# test_board_logic3.net
KiCad netlist of a schematic drawn in EAGLE
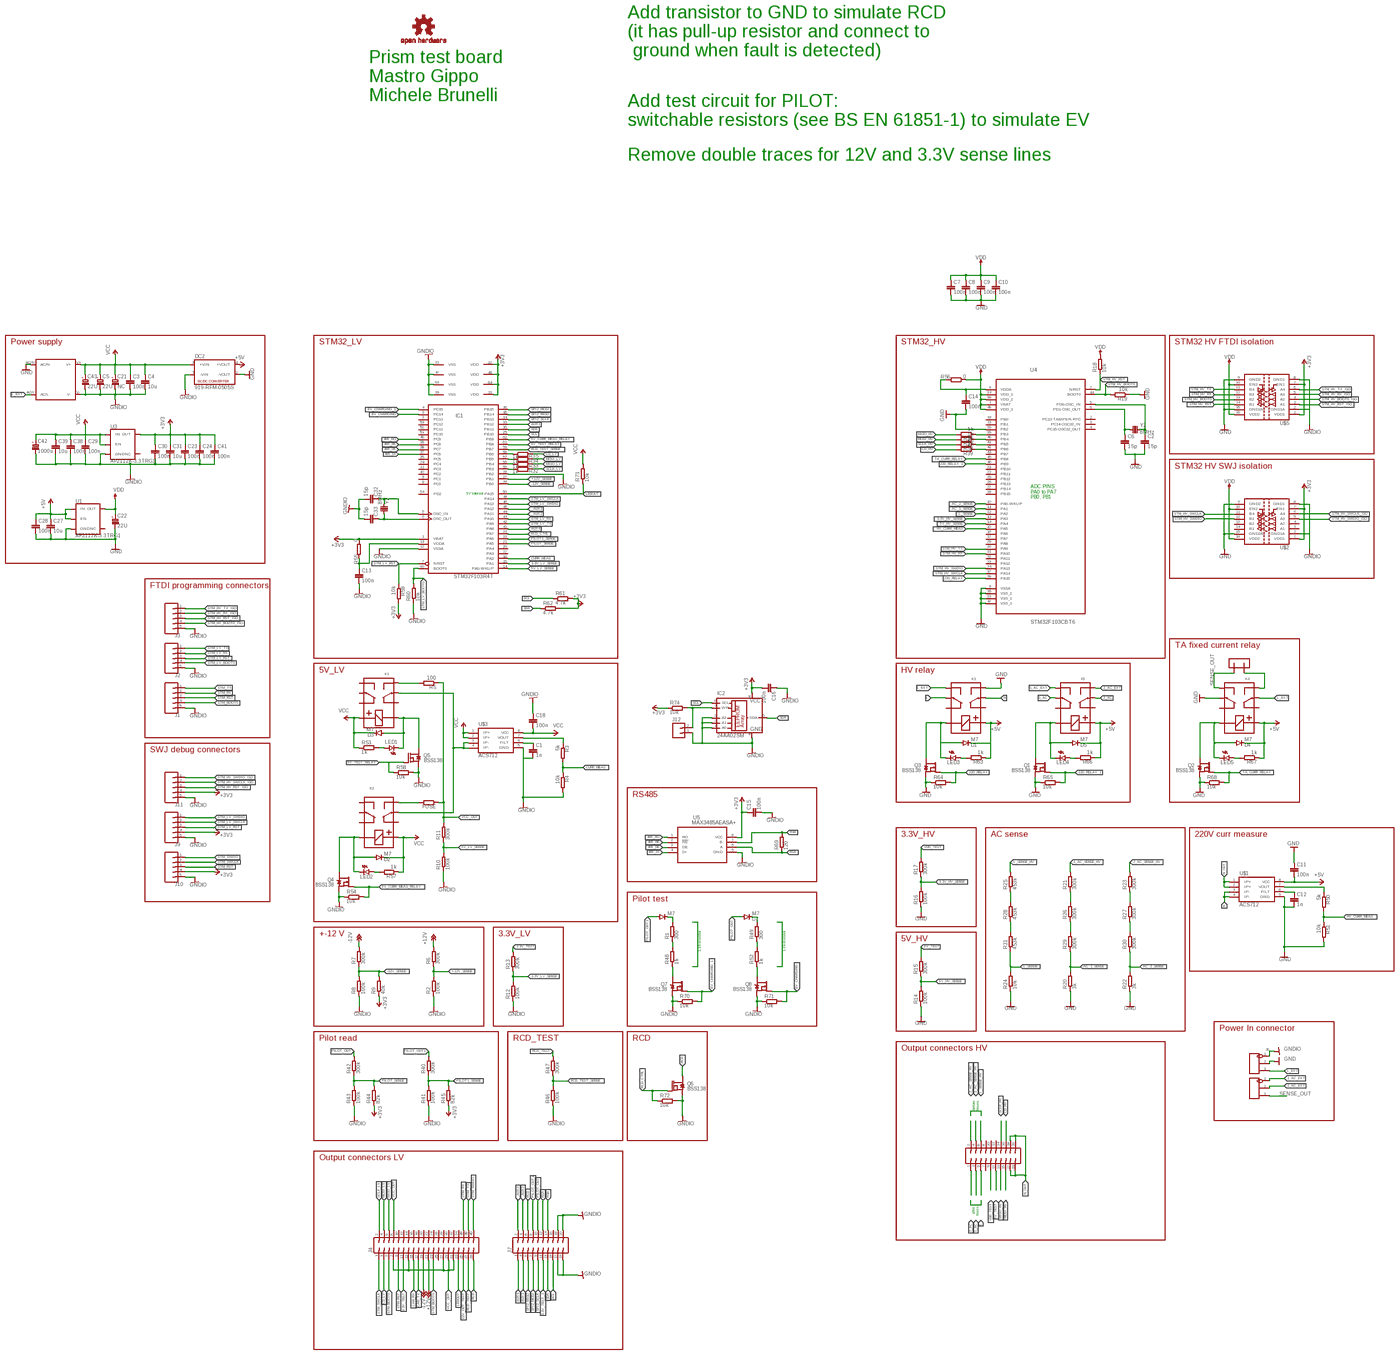
[diagram p0: schematic, sheet 1, overview]
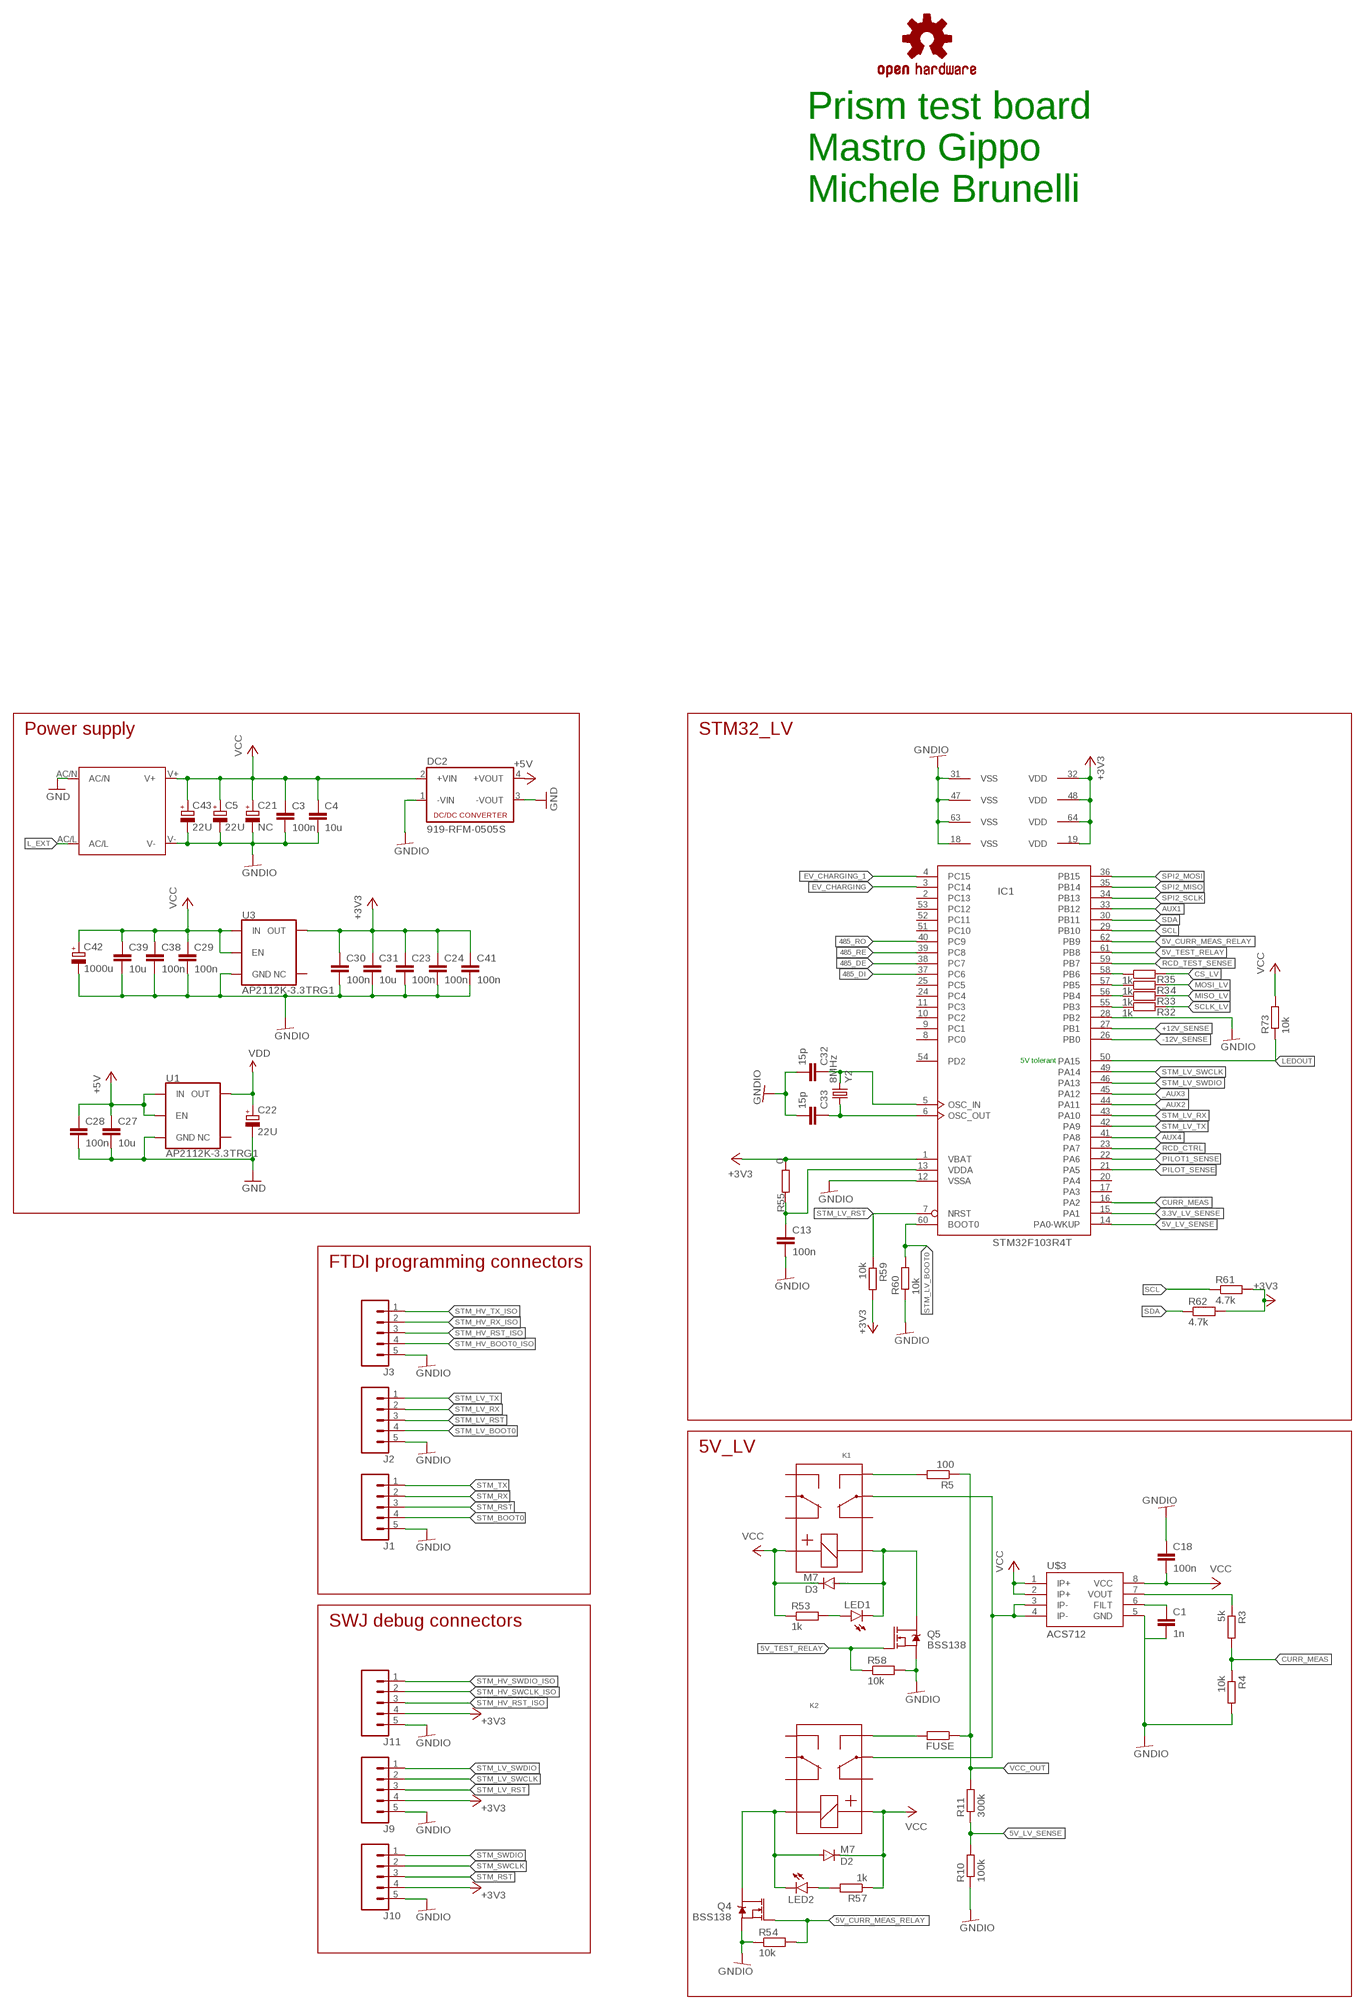
[diagram p1: schematic, sheet 1, part 1 of 4]
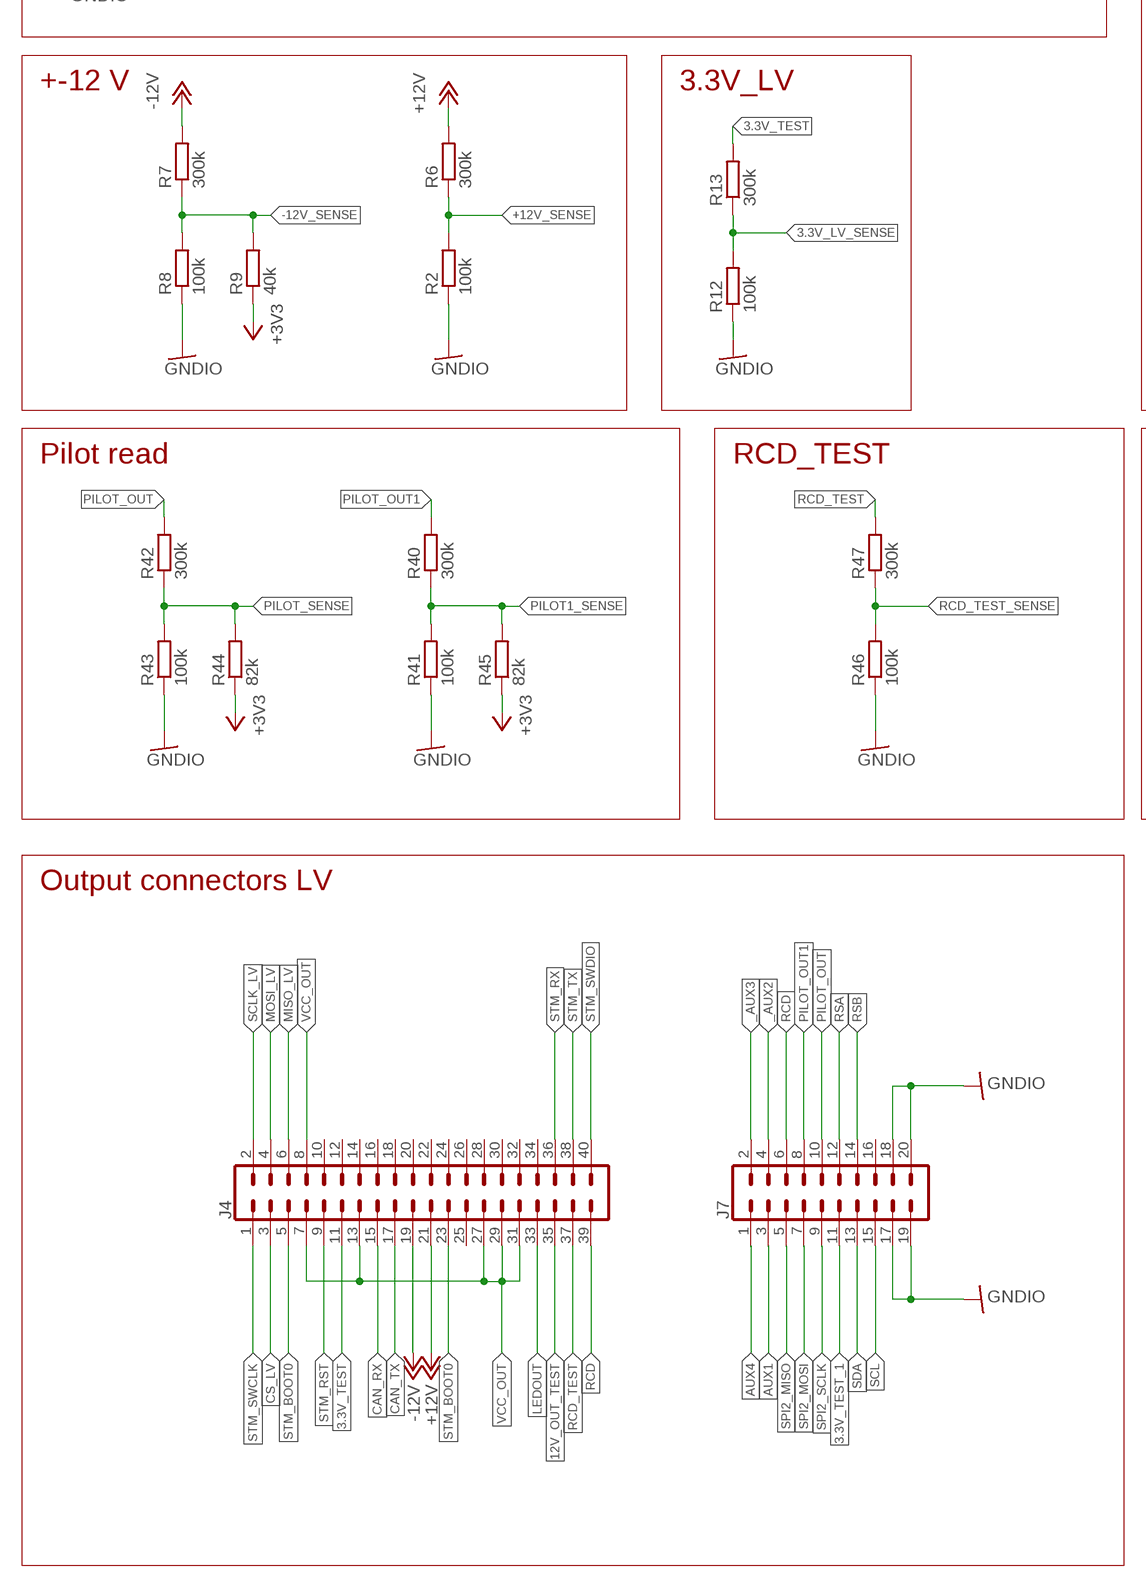
[diagram p2: schematic, sheet 1, part 2 of 4]
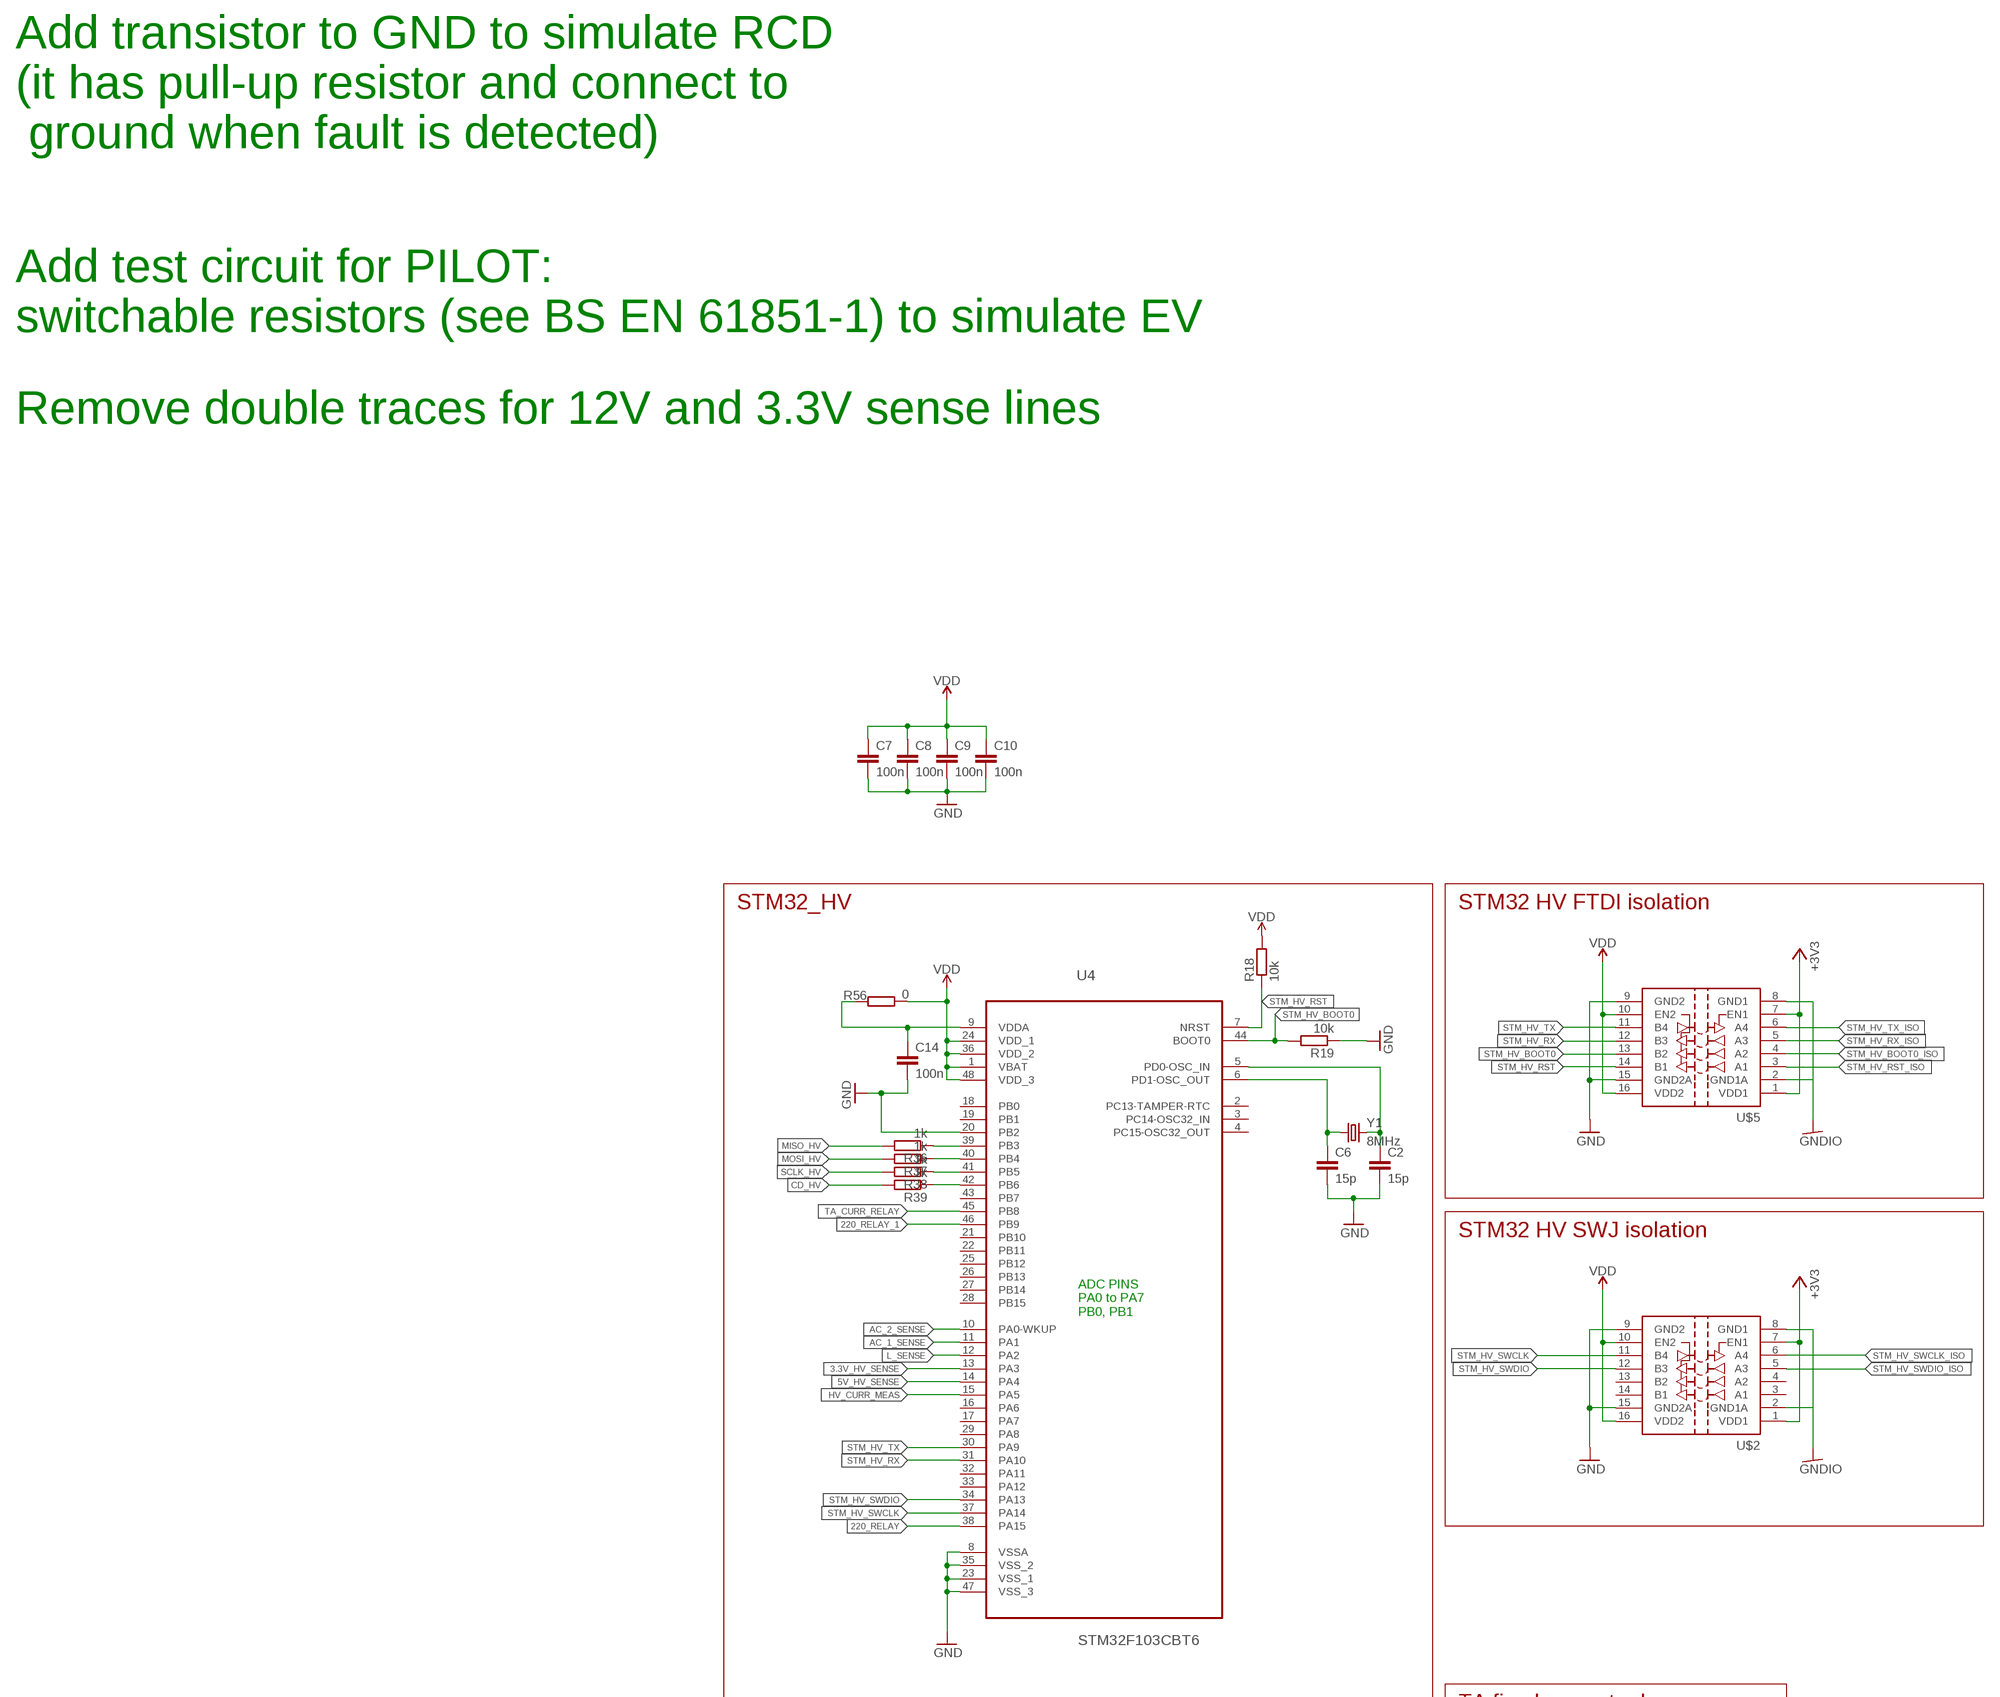
[diagram p3: schematic, sheet 1, part 3 of 4]
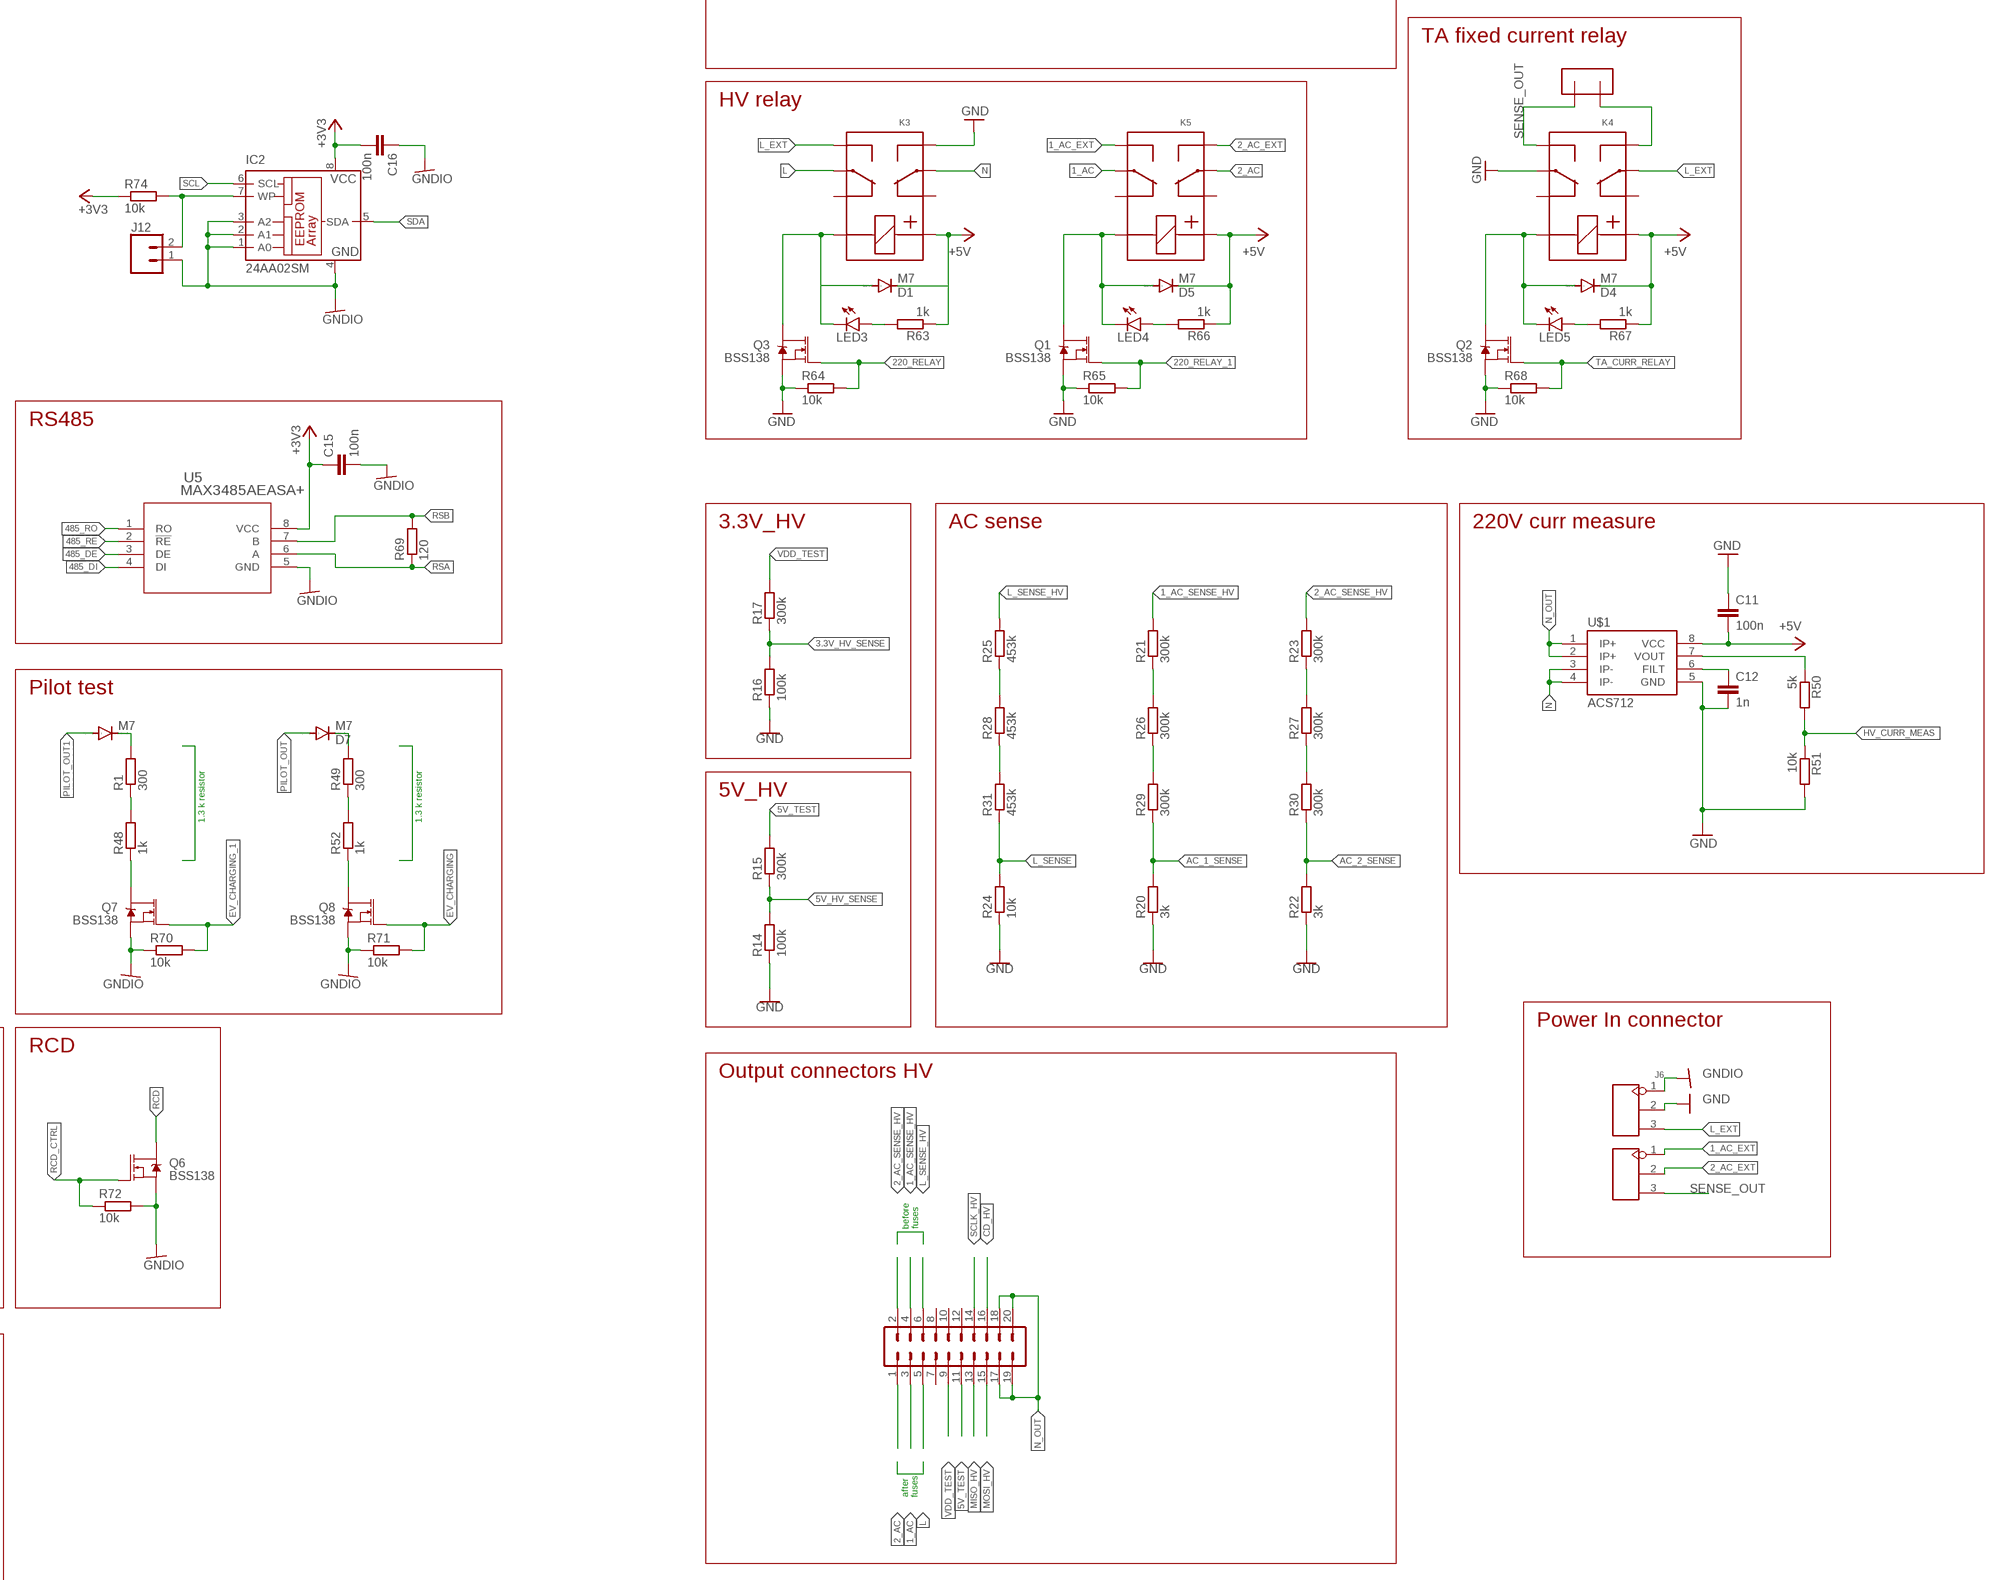
[diagram p4: schematic, sheet 1, part 4 of 4]

(export (version "E")
  (design (tool "Eeschema 10.0.6"))
  (components
    (comp (ref "C1")
      (value "1n")
      (footprint "eagle-import:C0603K")
      (libsource (lib "eagle-import") (part "C-EUC0603K"))
    )
    (comp (ref "C2")
      (value "15p")
      (footprint "eagle-import:C0603K")
      (libsource (lib "eagle-import") (part "C-EUC0603K"))
    )
    (comp (ref "C3")
      (value "100n")
      (footprint "eagle-import:C0603K")
      (libsource (lib "eagle-import") (part "C-EUC0603K"))
    )
    (comp (ref "C4")
      (value "10u")
      (footprint "eagle-import:C0805K")
      (libsource (lib "eagle-import") (part "resistor_348_C-EUC0805K"))
    )
    (comp (ref "C5")
      (value "22U")
      (footprint "eagle-import:B_3528-21R")
      (libsource (lib "eagle-import") (part "CPOL-EUB/3528-21R"))
    )
    (comp (ref "C6")
      (value "15p")
      (footprint "eagle-import:C0603K")
      (libsource (lib "eagle-import") (part "C-EUC0603K"))
    )
    (comp (ref "C7")
      (value "100n")
      (footprint "eagle-import:C0603K")
      (libsource (lib "eagle-import") (part "C-EUC0603K"))
    )
    (comp (ref "C8")
      (value "100n")
      (footprint "eagle-import:C0603K")
      (libsource (lib "eagle-import") (part "C-EUC0603K"))
    )
    (comp (ref "C9")
      (value "100n")
      (footprint "eagle-import:C0603K")
      (libsource (lib "eagle-import") (part "C-EUC0603K"))
    )
    (comp (ref "C10")
      (value "100n")
      (footprint "eagle-import:C0603K")
      (libsource (lib "eagle-import") (part "C-EUC0603K"))
    )
    (comp (ref "C11")
      (value "100n")
      (footprint "eagle-import:C0603K")
      (libsource (lib "eagle-import") (part "C-EUC0603K"))
    )
    (comp (ref "C12")
      (value "1n")
      (footprint "eagle-import:C0603K")
      (libsource (lib "eagle-import") (part "C-EUC0603K"))
    )
    (comp (ref "C13")
      (value "100n")
      (footprint "eagle-import:C0603K")
      (libsource (lib "eagle-import") (part "C-EUC0603K"))
    )
    (comp (ref "C14")
      (value "100n")
      (footprint "eagle-import:C0603K")
      (libsource (lib "eagle-import") (part "C-EUC0603K"))
    )
    (comp (ref "C15")
      (value "100n")
      (footprint "eagle-import:C0603K")
      (libsource (lib "eagle-import") (part "C-EUC0603K"))
    )
    (comp (ref "C16")
      (value "100n")
      (footprint "eagle-import:C0603K")
      (libsource (lib "eagle-import") (part "C-EUC0603K"))
    )
    (comp (ref "C18")
      (value "100n")
      (footprint "eagle-import:C0603K")
      (libsource (lib "eagle-import") (part "C-EUC0603K"))
    )
    (comp (ref "C21")
      (value "NC")
      (footprint "eagle-import:153CLV-0505")
      (libsource (lib "eagle-import") (part "CPOL-EU153CLV-0505"))
    )
    (comp (ref "C22")
      (value "22U")
      (footprint "eagle-import:B_3528-21R")
      (libsource (lib "eagle-import") (part "CPOL-EUB/3528-21R"))
    )
    (comp (ref "C23")
      (value "100n")
      (footprint "eagle-import:C0603K")
      (libsource (lib "eagle-import") (part "C-EUC0603K"))
    )
    (comp (ref "C24")
      (value "100n")
      (footprint "eagle-import:C0603K")
      (libsource (lib "eagle-import") (part "C-EUC0603K"))
    )
    (comp (ref "C27")
      (value "10u")
      (footprint "eagle-import:C0805K")
      (libsource (lib "eagle-import") (part "resistor_348_C-EUC0805K"))
    )
    (comp (ref "C28")
      (value "100n")
      (footprint "eagle-import:C0603K")
      (libsource (lib "eagle-import") (part "C-EUC0603K"))
    )
    (comp (ref "C29")
      (value "100n")
      (footprint "eagle-import:C0603K")
      (libsource (lib "eagle-import") (part "C-EUC0603K"))
    )
    (comp (ref "C30")
      (value "100n")
      (footprint "eagle-import:C0603K")
      (libsource (lib "eagle-import") (part "C-EUC0603K"))
    )
    (comp (ref "C31")
      (value "10u")
      (footprint "eagle-import:C0805K")
      (libsource (lib "eagle-import") (part "resistor_348_C-EUC0805K"))
    )
    (comp (ref "C32")
      (value "15p")
      (footprint "eagle-import:C0603K")
      (libsource (lib "eagle-import") (part "C-EUC0603K"))
    )
    (comp (ref "C33")
      (value "15p")
      (footprint "eagle-import:C0603K")
      (libsource (lib "eagle-import") (part "C-EUC0603K"))
    )
    (comp (ref "C38")
      (value "100n")
      (footprint "eagle-import:C0603K")
      (libsource (lib "eagle-import") (part "C-EUC0603K"))
    )
    (comp (ref "C39")
      (value "10u")
      (footprint "eagle-import:C0805K")
      (libsource (lib "eagle-import") (part "resistor_348_C-EUC0805K"))
    )
    (comp (ref "C41")
      (value "100n")
      (footprint "eagle-import:C0603K")
      (libsource (lib "eagle-import") (part "C-EUC0603K"))
    )
    (comp (ref "C42")
      (value "1000u")
      (footprint "eagle-import:E5-10,5")
      (libsource (lib "eagle-import") (part "CPOL-EUE5-10.5"))
    )
    (comp (ref "C43")
      (value "22U")
      (footprint "eagle-import:B_3528-21R")
      (libsource (lib "eagle-import") (part "CPOL-EUB/3528-21R"))
    )
    (comp (ref "D1")
      (value "M7")
      (footprint "eagle-import:DO-214AC")
      (libsource (lib "eagle-import") (part "DIODE-DO-214AC"))
    )
    (comp (ref "D2")
      (value "M7")
      (footprint "eagle-import:DO-214AC")
      (libsource (lib "eagle-import") (part "DIODE-DO-214AC"))
    )
    (comp (ref "D3")
      (value "M7")
      (footprint "eagle-import:DO-214AC")
      (libsource (lib "eagle-import") (part "DIODE-DO-214AC"))
    )
    (comp (ref "D4")
      (value "M7")
      (footprint "eagle-import:DO-214AC")
      (libsource (lib "eagle-import") (part "DIODE-DO-214AC"))
    )
    (comp (ref "D5")
      (value "M7")
      (footprint "eagle-import:DO-214AC")
      (libsource (lib "eagle-import") (part "DIODE-DO-214AC"))
    )
    (comp (ref "D6")
      (value "M7")
      (footprint "eagle-import:DO-214AC")
      (libsource (lib "eagle-import") (part "DIODE-DO-214AC"))
    )
    (comp (ref "D7")
      (value "M7")
      (footprint "eagle-import:DO-214AC")
      (libsource (lib "eagle-import") (part "DIODE-DO-214AC"))
    )
    (comp (ref "DC2")
      (value "919-RFM-0505S")
      (footprint "eagle-import:NME")
      (fields (field (name "MF") "C & D TECHNOLOGIES, INC") (field (name "MPN") "NME1205D"))
      (libsource (lib "eagle-import") (part "NME"))
    )
    (comp (ref "FUSE")
      (value "R-EU_R0805")
      (footprint "eagle-import:R0805")
      (libsource (lib "eagle-import") (part "R-EU_R0805"))
    )
    (comp (ref "IC1")
      (value "STM32F103R4T")
      (footprint "eagle-import:LQFP64")
      (libsource (lib "eagle-import") (part "STM32F103RT4"))
    )
    (comp (ref "IC2")
      (value "24AA02SM")
      (footprint "eagle-import:SO-08M")
      (fields (field (name "MF") "MICROCHIP") (field (name "MPN") "24AA02-I/SN"))
      (libsource (lib "eagle-import") (part "24SMAA02"))
    )
    (comp (ref "J1")
      (value "2001R-5P")
      (footprint "eagle-import:JST-5-PTH-VERT")
      (libsource (lib "eagle-import") (part "CONN_05JST-VERT"))
    )
    (comp (ref "J2")
      (value "2001R-5P")
      (footprint "eagle-import:JST-5-PTH-VERT")
      (libsource (lib "eagle-import") (part "CONN_05JST-VERT"))
    )
    (comp (ref "J3")
      (value "2001R-5P")
      (footprint "eagle-import:JST-5-PTH-VERT")
      (libsource (lib "eagle-import") (part "CONN_05JST-VERT"))
    )
    (comp (ref "J4")
      (value "CONN_20X2SHROUDED")
      (footprint "eagle-import:2X20_SHROUDED")
      (libsource (lib "eagle-import") (part "CONN_20X2SHROUDED"))
    )
    (comp (ref "J5")
      (value "GREEN-3P-5.0")
      (footprint "eagle-import:H3-5.0-15.5X8.0MM")
      (libsource (lib "eagle-import") (part "SCREW-TERMINAL-GREEN(3P-5.0)"))
    )
    (comp (ref "J6")
      (value "GREEN-3P-5.0")
      (footprint "eagle-import:H3-5.0-15.5X8.0MM")
      (libsource (lib "eagle-import") (part "SCREW-TERMINAL-GREEN(3P-5.0)"))
    )
    (comp (ref "J7")
      (value "CONN_10X2")
      (footprint "eagle-import:2X10")
      (libsource (lib "eagle-import") (part "CONN_10X2"))
    )
    (comp (ref "J8")
      (value "CONN_10X2")
      (footprint "eagle-import:2X10")
      (libsource (lib "eagle-import") (part "CONN_10X2"))
    )
    (comp (ref "J9")
      (value "2001R-5P")
      (footprint "eagle-import:JST-5-PTH-VERT")
      (libsource (lib "eagle-import") (part "CONN_05JST-VERT"))
    )
    (comp (ref "J10")
      (value "2001R-5P")
      (footprint "eagle-import:JST-5-PTH-VERT")
      (libsource (lib "eagle-import") (part "CONN_05JST-VERT"))
    )
    (comp (ref "J11")
      (value "2001R-5P")
      (footprint "eagle-import:JST-5-PTH-VERT")
      (libsource (lib "eagle-import") (part "CONN_05JST-VERT"))
    )
    (comp (ref "J12")
      (value "CONN_02")
      (footprint "eagle-import:1X02")
      (libsource (lib "eagle-import") (part "CONN_02"))
    )
    (comp (ref "K1")
      (value "G6S-2")
      (footprint "eagle-import:G6S-2")
      (libsource (lib "eagle-import") (part "G6S-2"))
    )
    (comp (ref "K2")
      (value "G6S-2")
      (footprint "eagle-import:G6S-2")
      (libsource (lib "eagle-import") (part "G6S-2"))
    )
    (comp (ref "K3")
      (value "G6S-2")
      (footprint "eagle-import:G6S-2")
      (libsource (lib "eagle-import") (part "G6S-2"))
    )
    (comp (ref "K4")
      (value "G6S-2")
      (footprint "eagle-import:G6S-2")
      (libsource (lib "eagle-import") (part "G6S-2"))
    )
    (comp (ref "K5")
      (value "G6S-2")
      (footprint "eagle-import:G6S-2")
      (libsource (lib "eagle-import") (part "G6S-2"))
    )
    (comp (ref "LED1")
      (value "LEDSMT1206")
      (footprint "eagle-import:1206")
      (libsource (lib "eagle-import") (part "LEDSMT1206"))
    )
    (comp (ref "LED2")
      (value "LEDSMT1206")
      (footprint "eagle-import:1206")
      (libsource (lib "eagle-import") (part "LEDSMT1206"))
    )
    (comp (ref "LED3")
      (value "LEDSMT1206")
      (footprint "eagle-import:1206")
      (libsource (lib "eagle-import") (part "LEDSMT1206"))
    )
    (comp (ref "LED4")
      (value "LEDSMT1206")
      (footprint "eagle-import:1206")
      (libsource (lib "eagle-import") (part "LEDSMT1206"))
    )
    (comp (ref "LED5")
      (value "LEDSMT1206")
      (footprint "eagle-import:1206")
      (libsource (lib "eagle-import") (part "LEDSMT1206"))
    )
    (comp (ref "Q1")
      (value "BSS138")
      (footprint "eagle-import:SOT23-3")
      (libsource (lib "eagle-import") (part "MOSFET-NCH-BSS138"))
    )
    (comp (ref "Q2")
      (value "BSS138")
      (footprint "eagle-import:SOT23-3")
      (libsource (lib "eagle-import") (part "MOSFET-NCH-BSS138"))
    )
    (comp (ref "Q3")
      (value "BSS138")
      (footprint "eagle-import:SOT23-3")
      (libsource (lib "eagle-import") (part "MOSFET-NCH-BSS138"))
    )
    (comp (ref "Q4")
      (value "BSS138")
      (footprint "eagle-import:SOT23-3")
      (libsource (lib "eagle-import") (part "MOSFET-NCH-BSS138"))
    )
    (comp (ref "Q5")
      (value "BSS138")
      (footprint "eagle-import:SOT23-3")
      (libsource (lib "eagle-import") (part "MOSFET-NCH-BSS138"))
    )
    (comp (ref "Q6")
      (value "BSS138")
      (footprint "eagle-import:SOT23-3")
      (libsource (lib "eagle-import") (part "MOSFET-NCH-BSS138"))
    )
    (comp (ref "Q7")
      (value "BSS138")
      (footprint "eagle-import:SOT23-3")
      (libsource (lib "eagle-import") (part "MOSFET-NCH-BSS138"))
    )
    (comp (ref "Q8")
      (value "BSS138")
      (footprint "eagle-import:SOT23-3")
      (libsource (lib "eagle-import") (part "MOSFET-NCH-BSS138"))
    )
    (comp (ref "R1")
      (value "300")
      (footprint "eagle-import:R0603")
      (libsource (lib "eagle-import") (part "R-EU_R0603"))
    )
    (comp (ref "R2")
      (value "100k")
      (footprint "eagle-import:R0603")
      (libsource (lib "eagle-import") (part "R-EU_R0603"))
    )
    (comp (ref "R3")
      (value "5k")
      (footprint "eagle-import:R0603")
      (libsource (lib "eagle-import") (part "R-EU_R0603"))
    )
    (comp (ref "R4")
      (value "10k")
      (footprint "eagle-import:R0603")
      (libsource (lib "eagle-import") (part "R-EU_R0603"))
    )
    (comp (ref "R5")
      (value "100")
      (footprint "eagle-import:R1210")
      (libsource (lib "eagle-import") (part "R-EU_R1210"))
    )
    (comp (ref "R6")
      (value "300k")
      (footprint "eagle-import:R0603")
      (libsource (lib "eagle-import") (part "R-EU_R0603"))
    )
    (comp (ref "R7")
      (value "300k")
      (footprint "eagle-import:R0603")
      (libsource (lib "eagle-import") (part "R-EU_R0603"))
    )
    (comp (ref "R8")
      (value "100k")
      (footprint "eagle-import:R0603")
      (libsource (lib "eagle-import") (part "R-EU_R0603"))
    )
    (comp (ref "R9")
      (value "40k")
      (footprint "eagle-import:R0603")
      (libsource (lib "eagle-import") (part "R-EU_R0603"))
    )
    (comp (ref "R10")
      (value "100k")
      (footprint "eagle-import:R0603")
      (libsource (lib "eagle-import") (part "R-EU_R0603"))
    )
    (comp (ref "R11")
      (value "300k")
      (footprint "eagle-import:R0603")
      (libsource (lib "eagle-import") (part "R-EU_R0603"))
    )
    (comp (ref "R12")
      (value "100k")
      (footprint "eagle-import:R0603")
      (libsource (lib "eagle-import") (part "R-EU_R0603"))
    )
    (comp (ref "R13")
      (value "300k")
      (footprint "eagle-import:R0603")
      (libsource (lib "eagle-import") (part "R-EU_R0603"))
    )
    (comp (ref "R14")
      (value "100k")
      (footprint "eagle-import:R0603")
      (libsource (lib "eagle-import") (part "R-EU_R0603"))
    )
    (comp (ref "R15")
      (value "300k")
      (footprint "eagle-import:R0603")
      (libsource (lib "eagle-import") (part "R-EU_R0603"))
    )
    (comp (ref "R16")
      (value "100k")
      (footprint "eagle-import:R0603")
      (libsource (lib "eagle-import") (part "R-EU_R0603"))
    )
    (comp (ref "R17")
      (value "300k")
      (footprint "eagle-import:R0603")
      (libsource (lib "eagle-import") (part "R-EU_R0603"))
    )
    (comp (ref "R18")
      (value "10k")
      (footprint "eagle-import:R0603")
      (libsource (lib "eagle-import") (part "R-EU_R0603"))
    )
    (comp (ref "R19")
      (value "10k")
      (footprint "eagle-import:R0603")
      (libsource (lib "eagle-import") (part "R-EU_R0603"))
    )
    (comp (ref "R20")
      (value "3k")
      (footprint "eagle-import:R0603")
      (libsource (lib "eagle-import") (part "R-EU_R0603"))
    )
    (comp (ref "R21")
      (value "300k")
      (footprint "eagle-import:R0603")
      (libsource (lib "eagle-import") (part "R-EU_R0603"))
    )
    (comp (ref "R22")
      (value "3k")
      (footprint "eagle-import:R0603")
      (libsource (lib "eagle-import") (part "R-EU_R0603"))
    )
    (comp (ref "R23")
      (value "300k")
      (footprint "eagle-import:R0603")
      (libsource (lib "eagle-import") (part "R-EU_R0603"))
    )
    (comp (ref "R24")
      (value "10k")
      (footprint "eagle-import:R0603")
      (libsource (lib "eagle-import") (part "R-EU_R0603"))
    )
    (comp (ref "R25")
      (value "453k")
      (footprint "eagle-import:R0603")
      (libsource (lib "eagle-import") (part "R-EU_R0603"))
    )
    (comp (ref "R26")
      (value "300k")
      (footprint "eagle-import:R0603")
      (libsource (lib "eagle-import") (part "R-EU_R0603"))
    )
    (comp (ref "R27")
      (value "300k")
      (footprint "eagle-import:R0603")
      (libsource (lib "eagle-import") (part "R-EU_R0603"))
    )
    (comp (ref "R28")
      (value "453k")
      (footprint "eagle-import:R0603")
      (libsource (lib "eagle-import") (part "R-EU_R0603"))
    )
    (comp (ref "R29")
      (value "300k")
      (footprint "eagle-import:R0603")
      (libsource (lib "eagle-import") (part "R-EU_R0603"))
    )
    (comp (ref "R30")
      (value "300k")
      (footprint "eagle-import:R0603")
      (libsource (lib "eagle-import") (part "R-EU_R0603"))
    )
    (comp (ref "R31")
      (value "453k")
      (footprint "eagle-import:R0603")
      (libsource (lib "eagle-import") (part "R-EU_R0603"))
    )
    (comp (ref "R32")
      (value "1k")
      (footprint "eagle-import:R0603")
      (libsource (lib "eagle-import") (part "R-EU_R0603"))
    )
    (comp (ref "R33")
      (value "1k")
      (footprint "eagle-import:R0603")
      (libsource (lib "eagle-import") (part "R-EU_R0603"))
    )
    (comp (ref "R34")
      (value "1k")
      (footprint "eagle-import:R0603")
      (libsource (lib "eagle-import") (part "R-EU_R0603"))
    )
    (comp (ref "R35")
      (value "1k")
      (footprint "eagle-import:R0603")
      (libsource (lib "eagle-import") (part "R-EU_R0603"))
    )
    (comp (ref "R36")
      (value "1k")
      (footprint "eagle-import:R0603")
      (libsource (lib "eagle-import") (part "R-EU_R0603"))
    )
    (comp (ref "R37")
      (value "1k")
      (footprint "eagle-import:R0603")
      (libsource (lib "eagle-import") (part "R-EU_R0603"))
    )
    (comp (ref "R38")
      (value "1k")
      (footprint "eagle-import:R0603")
      (libsource (lib "eagle-import") (part "R-EU_R0603"))
    )
    (comp (ref "R39")
      (value "1k")
      (footprint "eagle-import:R0603")
      (libsource (lib "eagle-import") (part "R-EU_R0603"))
    )
    (comp (ref "R40")
      (value "300k")
      (footprint "eagle-import:R0603")
      (libsource (lib "eagle-import") (part "R-EU_R0603"))
    )
    (comp (ref "R41")
      (value "100k")
      (footprint "eagle-import:R0603")
      (libsource (lib "eagle-import") (part "R-EU_R0603"))
    )
    (comp (ref "R42")
      (value "300k")
      (footprint "eagle-import:R0603")
      (libsource (lib "eagle-import") (part "R-EU_R0603"))
    )
    (comp (ref "R43")
      (value "100k")
      (footprint "eagle-import:R0603")
      (libsource (lib "eagle-import") (part "R-EU_R0603"))
    )
    (comp (ref "R44")
      (value "82k")
      (footprint "eagle-import:R0603")
      (libsource (lib "eagle-import") (part "R-EU_R0603"))
    )
    (comp (ref "R45")
      (value "82k")
      (footprint "eagle-import:R0603")
      (libsource (lib "eagle-import") (part "R-EU_R0603"))
    )
    (comp (ref "R46")
      (value "100k")
      (footprint "eagle-import:R0603")
      (libsource (lib "eagle-import") (part "R-EU_R0603"))
    )
    (comp (ref "R47")
      (value "300k")
      (footprint "eagle-import:R0603")
      (libsource (lib "eagle-import") (part "R-EU_R0603"))
    )
    (comp (ref "R48")
      (value "1k")
      (footprint "eagle-import:R0603")
      (libsource (lib "eagle-import") (part "R-EU_R0603"))
    )
    (comp (ref "R49")
      (value "300")
      (footprint "eagle-import:R0603")
      (libsource (lib "eagle-import") (part "R-EU_R0603"))
    )
    (comp (ref "R50")
      (value "5k")
      (footprint "eagle-import:R0603")
      (libsource (lib "eagle-import") (part "R-EU_R0603"))
    )
    (comp (ref "R51")
      (value "10k")
      (footprint "eagle-import:R0603")
      (libsource (lib "eagle-import") (part "R-EU_R0603"))
    )
    (comp (ref "R52")
      (value "1k")
      (footprint "eagle-import:R0603")
      (libsource (lib "eagle-import") (part "R-EU_R0603"))
    )
    (comp (ref "R53")
      (value "1k")
      (footprint "eagle-import:R0603")
      (libsource (lib "eagle-import") (part "R-EU_R0603"))
    )
    (comp (ref "R54")
      (value "10k")
      (footprint "eagle-import:R0603")
      (libsource (lib "eagle-import") (part "R-EU_R0603"))
    )
    (comp (ref "R55")
      (value "0")
      (footprint "eagle-import:R0603")
      (libsource (lib "eagle-import") (part "R-EU_R0603"))
    )
    (comp (ref "R56")
      (value "0")
      (footprint "eagle-import:R0603")
      (libsource (lib "eagle-import") (part "R-EU_R0603"))
    )
    (comp (ref "R57")
      (value "1k")
      (footprint "eagle-import:R0603")
      (libsource (lib "eagle-import") (part "R-EU_R0603"))
    )
    (comp (ref "R58")
      (value "10k")
      (footprint "eagle-import:R0603")
      (libsource (lib "eagle-import") (part "R-EU_R0603"))
    )
    (comp (ref "R59")
      (value "10k")
      (footprint "eagle-import:R0603")
      (libsource (lib "eagle-import") (part "R-EU_R0603"))
    )
    (comp (ref "R60")
      (value "10k")
      (footprint "eagle-import:R0603")
      (libsource (lib "eagle-import") (part "R-EU_R0603"))
    )
    (comp (ref "R61")
      (value "4.7k")
      (footprint "eagle-import:R0603")
      (libsource (lib "eagle-import") (part "R-EU_R0603"))
    )
    (comp (ref "R62")
      (value "4.7k")
      (footprint "eagle-import:R0603")
      (libsource (lib "eagle-import") (part "R-EU_R0603"))
    )
    (comp (ref "R63")
      (value "1k")
      (footprint "eagle-import:R0603")
      (libsource (lib "eagle-import") (part "R-EU_R0603"))
    )
    (comp (ref "R64")
      (value "10k")
      (footprint "eagle-import:R0603")
      (libsource (lib "eagle-import") (part "R-EU_R0603"))
    )
    (comp (ref "R65")
      (value "10k")
      (footprint "eagle-import:R0603")
      (libsource (lib "eagle-import") (part "R-EU_R0603"))
    )
    (comp (ref "R66")
      (value "1k")
      (footprint "eagle-import:R0603")
      (libsource (lib "eagle-import") (part "R-EU_R0603"))
    )
    (comp (ref "R67")
      (value "1k")
      (footprint "eagle-import:R0603")
      (libsource (lib "eagle-import") (part "R-EU_R0603"))
    )
    (comp (ref "R68")
      (value "10k")
      (footprint "eagle-import:R0603")
      (libsource (lib "eagle-import") (part "R-EU_R0603"))
    )
    (comp (ref "R69")
      (value "120")
      (footprint "eagle-import:R0603")
      (libsource (lib "eagle-import") (part "R-EU_R0603"))
    )
    (comp (ref "R70")
      (value "10k")
      (footprint "eagle-import:R0603")
      (libsource (lib "eagle-import") (part "R-EU_R0603"))
    )
    (comp (ref "R71")
      (value "10k")
      (footprint "eagle-import:R0603")
      (libsource (lib "eagle-import") (part "R-EU_R0603"))
    )
    (comp (ref "R72")
      (value "10k")
      (footprint "eagle-import:R0603")
      (libsource (lib "eagle-import") (part "R-EU_R0603"))
    )
    (comp (ref "R73")
      (value "10k")
      (footprint "eagle-import:R0603")
      (libsource (lib "eagle-import") (part "R-EU_R0603"))
    )
    (comp (ref "R74")
      (value "10k")
      (footprint "eagle-import:R0603")
      (libsource (lib "eagle-import") (part "R-EU_R0603"))
    )
    (comp (ref "U$1")
      (value "ACS712")
      (footprint "eagle-import:SO08")
      (libsource (lib "eagle-import") (part "ACS712"))
    )
    (comp (ref "U$2")
      (value "SI8441IS1")
      (footprint "eagle-import:SO16")
      (libsource (lib "eagle-import") (part "SI8441IS1"))
    )
    (comp (ref "U$3")
      (value "ACS712")
      (footprint "eagle-import:SO08")
      (libsource (lib "eagle-import") (part "ACS712"))
    )
    (comp (ref "U$4")
      (value "NC")
      (footprint "eagle-import:IRM_15_20")
      (libsource (lib "eagle-import") (part "IRM_15/20IRM_15/20"))
    )
    (comp (ref "U$5")
      (value "SI8441IS1")
      (footprint "eagle-import:SO16")
      (libsource (lib "eagle-import") (part "SI8441IS1"))
    )
    (comp (ref "U$6")
      (value "2 PIN STRIP F")
      (footprint "eagle-import:STRIP_NOMIDDLE")
      (libsource (lib "eagle-import") (part "ISOLATED_2P"))
    )
    (comp (ref "U$7")
      (value "OSHW-LOGOL")
      (footprint "eagle-import:OSHW-LOGO-L")
      (libsource (lib "eagle-import") (part "OSHW-LOGOL"))
    )
    (comp (ref "U1")
      (value "AP2112K-3.3TRG1")
      (footprint "eagle-import:SOT23-5")
      (libsource (lib "eagle-import") (part "V_REG_AP2112K-3.3V"))
    )
    (comp (ref "U3")
      (value "AP2112K-3.3TRG1")
      (footprint "eagle-import:SOT23-5")
      (libsource (lib "eagle-import") (part "V_REG_AP2112K-3.3V"))
    )
    (comp (ref "U4")
      (value "STM32F103CBT6")
      (footprint "eagle-import:QFP50P900X900X160-48N")
      (libsource (lib "eagle-import") (part "STM32F103CBT6"))
    )
    (comp (ref "U5")
      (value "MAX3485AEASA+")
      (footprint "eagle-import:21-0041B_8")
      (libsource (lib "eagle-import") (part "MAX3485AEASA+"))
    )
    (comp (ref "Y1")
      (value "8MHz")
      (footprint "eagle-import:CRYSTAL-SMD-3.2X2.5MM")
      (libsource (lib "eagle-import") (part "CRYSTALSMD-3.2X2.5"))
    )
    (comp (ref "Y2")
      (value "8MHz")
      (footprint "eagle-import:CRYSTAL-SMD-3.2X2.5MM")
      (libsource (lib "eagle-import") (part "CRYSTALSMD-3.2X2.5"))
    )
  )
  (nets
    (net (code "1") (name "+3V3") (class "Default")
      (node (ref "C15") (pin "1") (pinfunction "1_1") (pintype "passive"))
      (node (ref "C16") (pin "2") (pinfunction "2_2") (pintype "passive"))
      (node (ref "C23") (pin "1") (pinfunction "1_1") (pintype "passive"))
      (node (ref "C24") (pin "1") (pinfunction "1_1") (pintype "passive"))
      (node (ref "C30") (pin "1") (pinfunction "1_1") (pintype "passive"))
      (node (ref "C31") (pin "1") (pinfunction "1_1") (pintype "passive"))
      (node (ref "C41") (pin "1") (pinfunction "1_1") (pintype "passive"))
      (node (ref "IC1") (pin "1") (pinfunction "VBAT_1") (pintype "power_in"))
      (node (ref "IC1") (pin "19") (pinfunction "VDD_19") (pintype "power_in"))
      (node (ref "IC1") (pin "32") (pinfunction "VDD_32") (pintype "power_in"))
      (node (ref "IC1") (pin "48") (pinfunction "VDD_48") (pintype "power_in"))
      (node (ref "IC1") (pin "64") (pinfunction "VDD_64") (pintype "power_in"))
      (node (ref "IC2") (pin "8") (pinfunction "VCC_8") (pintype "power_in"))
      (node (ref "J10") (pin "4") (pinfunction "4_4") (pintype "passive"))
      (node (ref "J11") (pin "4") (pinfunction "4_4") (pintype "passive"))
      (node (ref "J9") (pin "4") (pinfunction "4_4") (pintype "passive"))
      (node (ref "R44") (pin "1") (pinfunction "1_1") (pintype "passive"))
      (node (ref "R45") (pin "1") (pinfunction "1_1") (pintype "passive"))
      (node (ref "R55") (pin "1") (pinfunction "1_1") (pintype "passive"))
      (node (ref "R59") (pin "2") (pinfunction "2_2") (pintype "passive"))
      (node (ref "R61") (pin "2") (pinfunction "2_2") (pintype "passive"))
      (node (ref "R62") (pin "2") (pinfunction "2_2") (pintype "passive"))
      (node (ref "R74") (pin "1") (pinfunction "1_1") (pintype "passive"))
      (node (ref "R9") (pin "1") (pinfunction "1_1") (pintype "passive"))
      (node (ref "U$2") (pin "1") (pinfunction "VDD1_1") (pintype "power_in"))
      (node (ref "U$2") (pin "7") (pinfunction "EN1_7") (pintype "input"))
      (node (ref "U$5") (pin "1") (pinfunction "VDD1_1") (pintype "power_in"))
      (node (ref "U$5") (pin "7") (pinfunction "EN1_7") (pintype "input"))
      (node (ref "U3") (pin "5") (pinfunction "OUT_5") (pintype "passive"))
      (node (ref "U5") (pin "8") (pinfunction "VCC_8") (pintype "power_in"))
    )
    (net (code "2") (name "+5V") (class "Default")
      (node (ref "C11") (pin "2") (pinfunction "2_2") (pintype "passive"))
      (node (ref "C27") (pin "1") (pinfunction "1_1") (pintype "passive"))
      (node (ref "C28") (pin "1") (pinfunction "1_1") (pintype "passive"))
      (node (ref "D1") (pin "C") (pinfunction "C_C") (pintype "passive"))
      (node (ref "D4") (pin "C") (pinfunction "C_C") (pintype "passive"))
      (node (ref "D5") (pin "C") (pinfunction "C_C") (pintype "passive"))
      (node (ref "DC2") (pin "4") (pinfunction "+VOUT_4") (pintype "passive"))
      (node (ref "K3") (pin "1") (pinfunction "1_1") (pintype "passive"))
      (node (ref "K4") (pin "1") (pinfunction "1_1") (pintype "passive"))
      (node (ref "K5") (pin "1") (pinfunction "1_1") (pintype "passive"))
      (node (ref "R63") (pin "1") (pinfunction "1_1") (pintype "passive"))
      (node (ref "R66") (pin "1") (pinfunction "1_1") (pintype "passive"))
      (node (ref "R67") (pin "1") (pinfunction "1_1") (pintype "passive"))
      (node (ref "U$1") (pin "8") (pinfunction "VCC_8") (pintype "bidirectional"))
      (node (ref "U1") (pin "1") (pinfunction "IN_1") (pintype "input"))
      (node (ref "U1") (pin "3") (pinfunction "EN_3") (pintype "input"))
    )
    (net (code "3") (name "+12V") (class "Default")
      (node (ref "J4") (pin "21") (pinfunction "21_21") (pintype "passive"))
      (node (ref "R6") (pin "2") (pinfunction "2_2") (pintype "passive"))
    )
    (net (code "4") (name "+12V_SENSE") (class "Default")
      (node (ref "IC1") (pin "27") (pinfunction "PB1_27") (pintype "bidirectional"))
      (node (ref "R2") (pin "2") (pinfunction "2_2") (pintype "passive"))
      (node (ref "R6") (pin "1") (pinfunction "1_1") (pintype "passive"))
    )
    (net (code "5") (name "-12V") (class "Default")
      (node (ref "J4") (pin "19") (pinfunction "19_19") (pintype "passive"))
      (node (ref "R7") (pin "2") (pinfunction "2_2") (pintype "passive"))
    )
    (net (code "6") (name "-12V_SENSE") (class "Default")
      (node (ref "IC1") (pin "26") (pinfunction "PB0_26") (pintype "bidirectional"))
      (node (ref "R7") (pin "1") (pinfunction "1_1") (pintype "passive"))
      (node (ref "R8") (pin "2") (pinfunction "2_2") (pintype "passive"))
      (node (ref "R9") (pin "2") (pinfunction "2_2") (pintype "passive"))
    )
    (net (code "7") (name "/PA11") (class "Default")
      (node (ref "U4") (pin "32") (pinfunction "PA11_32") (pintype "power_in"))
    )
    (net (code "8") (name "/SENSE_OUT") (class "Default")
      (node (ref "J5") (pin "3") (pinfunction "P$3_3") (pintype "bidirectional"))
      (node (ref "K4") (pin "8") (pinfunction "8_8") (pintype "passive"))
      (node (ref "U$6") (pin "P$2") (pinfunction "P$2_P$2") (pintype "bidirectional"))
    )
    (net (code "9") (name "1_AC") (class "Default")
      (node (ref "J8") (pin "3") (pinfunction "3_3") (pintype "passive"))
      (node (ref "K5") (pin "9") (pinfunction "9_9") (pintype "passive"))
    )
    (net (code "10") (name "1_AC_EXT") (class "Default")
      (node (ref "J5") (pin "1") (pinfunction "P$1_1") (pintype "bidirectional"))
      (node (ref "K5") (pin "8") (pinfunction "8_8") (pintype "passive"))
    )
    (net (code "11") (name "1_AC_SENSE_HV") (class "Default")
      (node (ref "J8") (pin "4") (pinfunction "4_4") (pintype "passive"))
      (node (ref "R21") (pin "2") (pinfunction "2_2") (pintype "passive"))
    )
    (net (code "12") (name "2_AC") (class "Default")
      (node (ref "J8") (pin "1") (pinfunction "1_1") (pintype "passive"))
      (node (ref "K5") (pin "4") (pinfunction "4_4") (pintype "passive"))
    )
    (net (code "13") (name "2_AC_EXT") (class "Default")
      (node (ref "J5") (pin "2") (pinfunction "P$2_2") (pintype "bidirectional"))
      (node (ref "K5") (pin "5") (pinfunction "5_5") (pintype "passive"))
    )
    (net (code "14") (name "2_AC_SENSE_HV") (class "Default")
      (node (ref "J8") (pin "2") (pinfunction "2_2") (pintype "passive"))
      (node (ref "R23") (pin "2") (pinfunction "2_2") (pintype "passive"))
    )
    (net (code "15") (name "3.3V_HV_SENSE") (class "Default")
      (node (ref "R16") (pin "2") (pinfunction "2_2") (pintype "passive"))
      (node (ref "R17") (pin "1") (pinfunction "1_1") (pintype "passive"))
      (node (ref "U4") (pin "13") (pinfunction "PA3_13") (pintype "bidirectional"))
    )
    (net (code "16") (name "3.3V_LV_SENSE") (class "Default")
      (node (ref "IC1") (pin "15") (pinfunction "PA1_15") (pintype "bidirectional"))
      (node (ref "R12") (pin "2") (pinfunction "2_2") (pintype "passive"))
      (node (ref "R13") (pin "1") (pinfunction "1_1") (pintype "passive"))
    )
    (net (code "17") (name "3.3V_TEST") (class "Default")
      (node (ref "J4") (pin "11") (pinfunction "11_11") (pintype "passive"))
      (node (ref "R13") (pin "2") (pinfunction "2_2") (pintype "passive"))
    )
    (net (code "18") (name "3.3V_TEST_1") (class "Default")
      (node (ref "J7") (pin "11") (pinfunction "11_11") (pintype "passive"))
    )
    (net (code "19") (name "5V_CURR_MEAS_RELAY") (class "Default")
      (node (ref "IC1") (pin "62") (pinfunction "PB9_62") (pintype "bidirectional"))
      (node (ref "Q4") (pin "1") (pinfunction "G_1") (pintype "bidirectional"))
      (node (ref "R54") (pin "2") (pinfunction "2_2") (pintype "passive"))
    )
    (net (code "20") (name "5V_HV_SENSE") (class "Default")
      (node (ref "R14") (pin "2") (pinfunction "2_2") (pintype "passive"))
      (node (ref "R15") (pin "1") (pinfunction "1_1") (pintype "passive"))
      (node (ref "U4") (pin "14") (pinfunction "PA4_14") (pintype "bidirectional"))
    )
    (net (code "21") (name "5V_LV_SENSE") (class "Default")
      (node (ref "IC1") (pin "14") (pinfunction "PA0-WKUP_14") (pintype "bidirectional"))
      (node (ref "R10") (pin "2") (pinfunction "2_2") (pintype "passive"))
      (node (ref "R11") (pin "1") (pinfunction "1_1") (pintype "passive"))
    )
    (net (code "22") (name "5V_TEST") (class "Default")
      (node (ref "J8") (pin "11") (pinfunction "11_11") (pintype "passive"))
      (node (ref "R15") (pin "2") (pinfunction "2_2") (pintype "passive"))
    )
    (net (code "23") (name "5V_TEST_RELAY") (class "Default")
      (node (ref "IC1") (pin "61") (pinfunction "PB8_61") (pintype "bidirectional"))
      (node (ref "Q5") (pin "1") (pinfunction "G_1") (pintype "bidirectional"))
      (node (ref "R58") (pin "1") (pinfunction "1_1") (pintype "passive"))
    )
    (net (code "24") (name "12V_OUT_TEST") (class "Default")
      (node (ref "J4") (pin "35") (pinfunction "35_35") (pintype "passive"))
    )
    (net (code "25") (name "220_RELAY") (class "Default")
      (node (ref "Q3") (pin "1") (pinfunction "G_1") (pintype "bidirectional"))
      (node (ref "R64") (pin "2") (pinfunction "2_2") (pintype "passive"))
      (node (ref "U4") (pin "38") (pinfunction "PA15_38") (pintype "bidirectional"))
    )
    (net (code "26") (name "220_RELAY_1") (class "Default")
      (node (ref "Q1") (pin "1") (pinfunction "G_1") (pintype "bidirectional"))
      (node (ref "R65") (pin "2") (pinfunction "2_2") (pintype "passive"))
      (node (ref "U4") (pin "46") (pinfunction "PB9_46") (pintype "bidirectional"))
    )
    (net (code "27") (name "485_DE") (class "Default")
      (node (ref "IC1") (pin "38") (pinfunction "PC7_38") (pintype "bidirectional"))
      (node (ref "U5") (pin "3") (pinfunction "DE_3") (pintype "passive"))
    )
    (net (code "28") (name "485_DI") (class "Default")
      (node (ref "IC1") (pin "37") (pinfunction "PC6_37") (pintype "bidirectional"))
      (node (ref "U5") (pin "4") (pinfunction "DI_4") (pintype "passive"))
    )
    (net (code "29") (name "485_RE") (class "Default")
      (node (ref "IC1") (pin "39") (pinfunction "PC8_39") (pintype "bidirectional"))
      (node (ref "U5") (pin "2") (pinfunction "~{RE}_2") (pintype "passive"))
    )
    (net (code "30") (name "485_RO") (class "Default")
      (node (ref "IC1") (pin "40") (pinfunction "PC9_40") (pintype "bidirectional"))
      (node (ref "U5") (pin "1") (pinfunction "RO_1") (pintype "passive"))
    )
    (net (code "31") (name "AC_1_SENSE") (class "Default")
      (node (ref "R20") (pin "2") (pinfunction "2_2") (pintype "passive"))
      (node (ref "R29") (pin "1") (pinfunction "1_1") (pintype "passive"))
      (node (ref "U4") (pin "11") (pinfunction "PA1_11") (pintype "bidirectional"))
    )
    (net (code "32") (name "AC_2_SENSE") (class "Default")
      (node (ref "R22") (pin "2") (pinfunction "2_2") (pintype "passive"))
      (node (ref "R30") (pin "1") (pinfunction "1_1") (pintype "passive"))
      (node (ref "U4") (pin "10") (pinfunction "PA0-WKUP_10") (pintype "bidirectional"))
    )
    (net (code "33") (name "AUX1") (class "Default")
      (node (ref "IC1") (pin "33") (pinfunction "PB12_33") (pintype "bidirectional"))
      (node (ref "J7") (pin "3") (pinfunction "3_3") (pintype "passive"))
    )
    (net (code "34") (name "AUX4") (class "Default")
      (node (ref "IC1") (pin "41") (pinfunction "PA8_41") (pintype "bidirectional"))
      (node (ref "J7") (pin "1") (pinfunction "1_1") (pintype "passive"))
    )
    (net (code "35") (name "CAN_RX") (class "Default")
      (node (ref "J4") (pin "15") (pinfunction "15_15") (pintype "passive"))
    )
    (net (code "36") (name "CAN_TX") (class "Default")
      (node (ref "J4") (pin "17") (pinfunction "17_17") (pintype "passive"))
    )
    (net (code "37") (name "CD_HV") (class "Default")
      (node (ref "J8") (pin "16") (pinfunction "16_16") (pintype "passive"))
      (node (ref "R39") (pin "2") (pinfunction "2_2") (pintype "passive"))
    )
    (net (code "38") (name "CS_LV") (class "Default")
      (node (ref "J4") (pin "3") (pinfunction "3_3") (pintype "passive"))
      (node (ref "R35") (pin "2") (pinfunction "2_2") (pintype "passive"))
    )
    (net (code "39") (name "CURR_MEAS") (class "Default")
      (node (ref "IC1") (pin "16") (pinfunction "PA2_16") (pintype "bidirectional"))
      (node (ref "R3") (pin "2") (pinfunction "2_2") (pintype "passive"))
      (node (ref "R4") (pin "1") (pinfunction "1_1") (pintype "passive"))
    )
    (net (code "40") (name "EV_CHARGING") (class "Default")
      (node (ref "IC1") (pin "3") (pinfunction "PC14_3") (pintype "bidirectional"))
      (node (ref "Q8") (pin "1") (pinfunction "G_1") (pintype "bidirectional"))
      (node (ref "R71") (pin "2") (pinfunction "2_2") (pintype "passive"))
    )
    (net (code "41") (name "EV_CHARGING_1") (class "Default")
      (node (ref "IC1") (pin "4") (pinfunction "PC15_4") (pintype "bidirectional"))
      (node (ref "Q7") (pin "1") (pinfunction "G_1") (pintype "bidirectional"))
      (node (ref "R70") (pin "2") (pinfunction "2_2") (pintype "passive"))
    )
    (net (code "42") (name "GND") (class "Default")
      (node (ref "C10") (pin "2") (pinfunction "2_2") (pintype "passive"))
      (node (ref "C11") (pin "1") (pinfunction "1_1") (pintype "passive"))
      (node (ref "C12") (pin "2") (pinfunction "2_2") (pintype "passive"))
      (node (ref "C14") (pin "2") (pinfunction "2_2") (pintype "passive"))
      (node (ref "C2") (pin "2") (pinfunction "2_2") (pintype "passive"))
      (node (ref "C22") (pin "-") (pinfunction "-_-") (pintype "passive"))
      (node (ref "C27") (pin "2") (pinfunction "2_2") (pintype "passive"))
      (node (ref "C28") (pin "2") (pinfunction "2_2") (pintype "passive"))
      (node (ref "C6") (pin "2") (pinfunction "2_2") (pintype "passive"))
      (node (ref "C7") (pin "2") (pinfunction "2_2") (pintype "passive"))
      (node (ref "C8") (pin "2") (pinfunction "2_2") (pintype "passive"))
      (node (ref "C9") (pin "2") (pinfunction "2_2") (pintype "passive"))
      (node (ref "DC2") (pin "3") (pinfunction "-VOUT_3") (pintype "passive"))
      (node (ref "J6") (pin "2") (pinfunction "P$2_2") (pintype "bidirectional"))
      (node (ref "K3") (pin "5") (pinfunction "5_5") (pintype "passive"))
      (node (ref "K4") (pin "9") (pinfunction "9_9") (pintype "passive"))
      (node (ref "Q1") (pin "2") (pinfunction "S_2") (pintype "bidirectional"))
      (node (ref "Q2") (pin "2") (pinfunction "S_2") (pintype "bidirectional"))
      (node (ref "Q3") (pin "2") (pinfunction "S_2") (pintype "bidirectional"))
      (node (ref "R14") (pin "1") (pinfunction "1_1") (pintype "passive"))
      (node (ref "R16") (pin "1") (pinfunction "1_1") (pintype "passive"))
      (node (ref "R19") (pin "1") (pinfunction "1_1") (pintype "passive"))
      (node (ref "R20") (pin "1") (pinfunction "1_1") (pintype "passive"))
      (node (ref "R22") (pin "1") (pinfunction "1_1") (pintype "passive"))
      (node (ref "R24") (pin "1") (pinfunction "1_1") (pintype "passive"))
      (node (ref "R51") (pin "2") (pinfunction "2_2") (pintype "passive"))
      (node (ref "R64") (pin "1") (pinfunction "1_1") (pintype "passive"))
      (node (ref "R65") (pin "1") (pinfunction "1_1") (pintype "passive"))
      (node (ref "R68") (pin "1") (pinfunction "1_1") (pintype "passive"))
      (node (ref "U$1") (pin "5") (pinfunction "GND_5") (pintype "bidirectional"))
      (node (ref "U$2") (pin "15") (pinfunction "GND2A_15") (pintype "power_in"))
      (node (ref "U$2") (pin "9") (pinfunction "GND2_9") (pintype "power_in"))
      (node (ref "U$4") (pin "AC/N") (pinfunction "AC/N_AC/N") (pintype "input"))
      (node (ref "U$5") (pin "15") (pinfunction "GND2A_15") (pintype "power_in"))
      (node (ref "U$5") (pin "9") (pinfunction "GND2_9") (pintype "power_in"))
      (node (ref "U1") (pin "2") (pinfunction "GND_2") (pintype "input"))
      (node (ref "U4") (pin "20") (pinfunction "PB2_20") (pintype "bidirectional"))
      (node (ref "U4") (pin "23") (pinfunction "VSS_1_23") (pintype "bidirectional"))
      (node (ref "U4") (pin "35") (pinfunction "VSS_2_35") (pintype "passive"))
      (node (ref "U4") (pin "47") (pinfunction "VSS_3_47") (pintype "passive"))
      (node (ref "U4") (pin "8") (pinfunction "VSSA_8") (pintype "passive"))
    )
    (net (code "43") (name "GNDIO") (class "Default")
      (node (ref "C1") (pin "2") (pinfunction "2_2") (pintype "passive"))
      (node (ref "C13") (pin "2") (pinfunction "2_2") (pintype "passive"))
      (node (ref "C15") (pin "2") (pinfunction "2_2") (pintype "passive"))
      (node (ref "C16") (pin "1") (pinfunction "1_1") (pintype "passive"))
      (node (ref "C18") (pin "1") (pinfunction "1_1") (pintype "passive"))
      (node (ref "C21") (pin "-") (pinfunction "-_-") (pintype "passive"))
      (node (ref "C23") (pin "2") (pinfunction "2_2") (pintype "passive"))
      (node (ref "C24") (pin "2") (pinfunction "2_2") (pintype "passive"))
      (node (ref "C29") (pin "2") (pinfunction "2_2") (pintype "passive"))
      (node (ref "C3") (pin "2") (pinfunction "2_2") (pintype "passive"))
      (node (ref "C30") (pin "2") (pinfunction "2_2") (pintype "passive"))
      (node (ref "C31") (pin "2") (pinfunction "2_2") (pintype "passive"))
      (node (ref "C32") (pin "2") (pinfunction "2_2") (pintype "passive"))
      (node (ref "C33") (pin "2") (pinfunction "2_2") (pintype "passive"))
      (node (ref "C38") (pin "2") (pinfunction "2_2") (pintype "passive"))
      (node (ref "C39") (pin "2") (pinfunction "2_2") (pintype "passive"))
      (node (ref "C4") (pin "2") (pinfunction "2_2") (pintype "passive"))
      (node (ref "C41") (pin "2") (pinfunction "2_2") (pintype "passive"))
      (node (ref "C42") (pin "-") (pinfunction "-_-") (pintype "passive"))
      (node (ref "C43") (pin "-") (pinfunction "-_-") (pintype "passive"))
      (node (ref "C5") (pin "-") (pinfunction "-_-") (pintype "passive"))
      (node (ref "DC2") (pin "1") (pinfunction "-VIN_1") (pintype "passive"))
      (node (ref "IC1") (pin "12") (pinfunction "VSSA_12") (pintype "power_in"))
      (node (ref "IC1") (pin "18") (pinfunction "VSS_18") (pintype "power_in"))
      (node (ref "IC1") (pin "28") (pinfunction "PB2_28") (pintype "bidirectional"))
      (node (ref "IC1") (pin "31") (pinfunction "VSS_31") (pintype "power_in"))
      (node (ref "IC1") (pin "47") (pinfunction "VSS_47") (pintype "power_in"))
      (node (ref "IC1") (pin "63") (pinfunction "VSS_63") (pintype "power_in"))
      (node (ref "IC2") (pin "1") (pinfunction "A0_1") (pintype "input"))
      (node (ref "IC2") (pin "2") (pinfunction "A1_2") (pintype "input"))
      (node (ref "IC2") (pin "3") (pinfunction "A2_3") (pintype "input"))
      (node (ref "IC2") (pin "4") (pinfunction "GND_4") (pintype "power_in"))
      (node (ref "J1") (pin "5") (pinfunction "5_5") (pintype "passive"))
      (node (ref "J10") (pin "5") (pinfunction "5_5") (pintype "passive"))
      (node (ref "J11") (pin "5") (pinfunction "5_5") (pintype "passive"))
      (node (ref "J12") (pin "1") (pinfunction "1_1") (pintype "passive"))
      (node (ref "J2") (pin "5") (pinfunction "5_5") (pintype "passive"))
      (node (ref "J3") (pin "5") (pinfunction "5_5") (pintype "passive"))
      (node (ref "J6") (pin "1") (pinfunction "P$1_1") (pintype "bidirectional"))
      (node (ref "J7") (pin "17") (pinfunction "17_17") (pintype "passive"))
      (node (ref "J7") (pin "18") (pinfunction "18_18") (pintype "passive"))
      (node (ref "J7") (pin "19") (pinfunction "19_19") (pintype "passive"))
      (node (ref "J7") (pin "20") (pinfunction "20_20") (pintype "passive"))
      (node (ref "J9") (pin "5") (pinfunction "5_5") (pintype "passive"))
      (node (ref "Q4") (pin "2") (pinfunction "S_2") (pintype "bidirectional"))
      (node (ref "Q5") (pin "2") (pinfunction "S_2") (pintype "bidirectional"))
      (node (ref "Q6") (pin "2") (pinfunction "S_2") (pintype "bidirectional"))
      (node (ref "Q7") (pin "2") (pinfunction "S_2") (pintype "bidirectional"))
      (node (ref "Q8") (pin "2") (pinfunction "S_2") (pintype "bidirectional"))
      (node (ref "R10") (pin "1") (pinfunction "1_1") (pintype "passive"))
      (node (ref "R12") (pin "1") (pinfunction "1_1") (pintype "passive"))
      (node (ref "R2") (pin "1") (pinfunction "1_1") (pintype "passive"))
      (node (ref "R4") (pin "2") (pinfunction "2_2") (pintype "passive"))
      (node (ref "R41") (pin "1") (pinfunction "1_1") (pintype "passive"))
      (node (ref "R43") (pin "1") (pinfunction "1_1") (pintype "passive"))
      (node (ref "R46") (pin "1") (pinfunction "1_1") (pintype "passive"))
      (node (ref "R54") (pin "1") (pinfunction "1_1") (pintype "passive"))
      (node (ref "R58") (pin "2") (pinfunction "2_2") (pintype "passive"))
      (node (ref "R60") (pin "1") (pinfunction "1_1") (pintype "passive"))
      (node (ref "R70") (pin "1") (pinfunction "1_1") (pintype "passive"))
      (node (ref "R71") (pin "1") (pinfunction "1_1") (pintype "passive"))
      (node (ref "R72") (pin "2") (pinfunction "2_2") (pintype "passive"))
      (node (ref "R8") (pin "1") (pinfunction "1_1") (pintype "passive"))
      (node (ref "U$2") (pin "2") (pinfunction "GND1A_2") (pintype "power_in"))
      (node (ref "U$2") (pin "8") (pinfunction "GND1_8") (pintype "power_in"))
      (node (ref "U$3") (pin "5") (pinfunction "GND_5") (pintype "bidirectional"))
      (node (ref "U$4") (pin "V-") (pinfunction "V-_V-") (pintype "output"))
      (node (ref "U$5") (pin "2") (pinfunction "GND1A_2") (pintype "power_in"))
      (node (ref "U$5") (pin "8") (pinfunction "GND1_8") (pintype "power_in"))
      (node (ref "U3") (pin "2") (pinfunction "GND_2") (pintype "input"))
      (node (ref "U5") (pin "5") (pinfunction "GND_5") (pintype "passive"))
    )
    (net (code "44") (name "HV_CURR_MEAS") (class "Default")
      (node (ref "R50") (pin "2") (pinfunction "2_2") (pintype "passive"))
      (node (ref "R51") (pin "1") (pinfunction "1_1") (pintype "passive"))
      (node (ref "U4") (pin "15") (pinfunction "PA5_15") (pintype "bidirectional"))
    )
    (net (code "45") (name "L") (class "Default")
      (node (ref "J8") (pin "5") (pinfunction "5_5") (pintype "passive"))
      (node (ref "K3") (pin "9") (pinfunction "9_9") (pintype "passive"))
    )
    (net (code "46") (name "LEDOUT") (class "Default")
      (node (ref "IC1") (pin "50") (pinfunction "PA15_50") (pintype "bidirectional"))
      (node (ref "J4") (pin "33") (pinfunction "33_33") (pintype "passive"))
      (node (ref "R73") (pin "1") (pinfunction "1_1") (pintype "passive"))
    )
    (net (code "47") (name "L_EXT") (class "Default")
      (node (ref "J6") (pin "3") (pinfunction "P$3_3") (pintype "bidirectional"))
      (node (ref "K3") (pin "8") (pinfunction "8_8") (pintype "passive"))
      (node (ref "K4") (pin "4") (pinfunction "4_4") (pintype "passive"))
      (node (ref "U$4") (pin "AC/L") (pinfunction "AC/L_AC/L") (pintype "input"))
    )
    (net (code "48") (name "L_SENSE") (class "Default")
      (node (ref "R24") (pin "2") (pinfunction "2_2") (pintype "passive"))
      (node (ref "R31") (pin "1") (pinfunction "1_1") (pintype "passive"))
      (node (ref "U4") (pin "12") (pinfunction "PA2_12") (pintype "bidirectional"))
    )
    (net (code "49") (name "L_SENSE_HV") (class "Default")
      (node (ref "J8") (pin "6") (pinfunction "6_6") (pintype "passive"))
      (node (ref "R25") (pin "2") (pinfunction "2_2") (pintype "passive"))
    )
    (net (code "50") (name "MISO_HV") (class "Default")
      (node (ref "J8") (pin "13") (pinfunction "13_13") (pintype "passive"))
      (node (ref "R36") (pin "2") (pinfunction "2_2") (pintype "passive"))
    )
    (net (code "51") (name "MISO_LV") (class "Default")
      (node (ref "J4") (pin "6") (pinfunction "6_6") (pintype "passive"))
      (node (ref "R33") (pin "2") (pinfunction "2_2") (pintype "passive"))
    )
    (net (code "52") (name "MOSI_HV") (class "Default")
      (node (ref "J8") (pin "15") (pinfunction "15_15") (pintype "passive"))
      (node (ref "R37") (pin "2") (pinfunction "2_2") (pintype "passive"))
    )
    (net (code "53") (name "MOSI_LV") (class "Default")
      (node (ref "J4") (pin "4") (pinfunction "4_4") (pintype "passive"))
      (node (ref "R34") (pin "2") (pinfunction "2_2") (pintype "passive"))
    )
    (net (code "54") (name "N") (class "Default")
      (node (ref "K3") (pin "4") (pinfunction "4_4") (pintype "passive"))
      (node (ref "U$1") (pin "3") (pinfunction "IP-_3") (pintype "bidirectional"))
      (node (ref "U$1") (pin "4") (pinfunction "IP-_4") (pintype "bidirectional"))
    )
    (net (code "55") (name "N_OUT") (class "Default")
      (node (ref "J8") (pin "17") (pinfunction "17_17") (pintype "passive"))
      (node (ref "J8") (pin "18") (pinfunction "18_18") (pintype "passive"))
      (node (ref "J8") (pin "19") (pinfunction "19_19") (pintype "passive"))
      (node (ref "J8") (pin "20") (pinfunction "20_20") (pintype "passive"))
      (node (ref "U$1") (pin "1") (pinfunction "IP+_1") (pintype "bidirectional"))
      (node (ref "U$1") (pin "2") (pinfunction "IP+_2") (pintype "bidirectional"))
    )
    (net (code "56") (name "Net-(D6-PadC)") (class "Default")
      (node (ref "D6") (pin "C") (pinfunction "C_C") (pintype "passive"))
      (node (ref "R1") (pin "2") (pinfunction "2_2") (pintype "passive"))
    )
    (net (code "57") (name "Net-(D7-PadC)") (class "Default")
      (node (ref "D7") (pin "C") (pinfunction "C_C") (pintype "passive"))
      (node (ref "R49") (pin "2") (pinfunction "2_2") (pintype "passive"))
    )
    (net (code "58") (name "Net-(FUSE-Pad2)") (class "Default")
      (node (ref "FUSE") (pin "2") (pinfunction "2_2") (pintype "passive"))
      (node (ref "K2") (pin "5") (pinfunction "5_5") (pintype "passive"))
    )
    (net (code "59") (name "Net-(IC1A-OSC_IN)") (class "Default")
      (node (ref "C32") (pin "1") (pinfunction "1_1") (pintype "passive"))
      (node (ref "IC1") (pin "5") (pinfunction "OSC_IN_5") (pintype "bidirectional"))
      (node (ref "Y2") (pin "3") (pinfunction "2_3") (pintype "passive"))
    )
    (net (code "60") (name "Net-(IC1A-OSC_OUT)") (class "Default")
      (node (ref "C33") (pin "1") (pinfunction "1_1") (pintype "passive"))
      (node (ref "IC1") (pin "6") (pinfunction "OSC_OUT_6") (pintype "bidirectional"))
      (node (ref "Y2") (pin "1") (pinfunction "1_1") (pintype "passive"))
    )
    (net (code "61") (name "Net-(IC1A-PB3)") (class "Default")
      (node (ref "IC1") (pin "55") (pinfunction "PB3_55") (pintype "bidirectional"))
      (node (ref "R32") (pin "1") (pinfunction "1_1") (pintype "passive"))
    )
    (net (code "62") (name "Net-(IC1A-PB4)") (class "Default")
      (node (ref "IC1") (pin "56") (pinfunction "PB4_56") (pintype "bidirectional"))
      (node (ref "R33") (pin "1") (pinfunction "1_1") (pintype "passive"))
    )
    (net (code "63") (name "Net-(IC1A-PB5)") (class "Default")
      (node (ref "IC1") (pin "57") (pinfunction "PB5_57") (pintype "bidirectional"))
      (node (ref "R34") (pin "1") (pinfunction "1_1") (pintype "passive"))
    )
    (net (code "64") (name "Net-(IC1A-PB6)") (class "Default")
      (node (ref "IC1") (pin "58") (pinfunction "PB6_58") (pintype "bidirectional"))
      (node (ref "R35") (pin "1") (pinfunction "1_1") (pintype "passive"))
    )
    (net (code "65") (name "Net-(IC1A-VDDA)") (class "Default")
      (node (ref "C13") (pin "1") (pinfunction "1_1") (pintype "passive"))
      (node (ref "IC1") (pin "13") (pinfunction "VDDA_13") (pintype "power_in"))
      (node (ref "R55") (pin "2") (pinfunction "2_2") (pintype "passive"))
    )
    (net (code "66") (name "Net-(IC2-WP)") (class "Default")
      (node (ref "IC2") (pin "7") (pinfunction "WP_7") (pintype "input"))
      (node (ref "J12") (pin "2") (pinfunction "2_2") (pintype "passive"))
      (node (ref "R74") (pin "2") (pinfunction "2_2") (pintype "passive"))
    )
    (net (code "67") (name "Net-(K1-Pad8)") (class "Default")
      (node (ref "K1") (pin "8") (pinfunction "8_8") (pintype "passive"))
      (node (ref "R5") (pin "2") (pinfunction "2_2") (pintype "passive"))
    )
    (net (code "68") (name "Net-(K1-Pad9)") (class "Default")
      (node (ref "K1") (pin "9") (pinfunction "9_9") (pintype "passive"))
      (node (ref "K2") (pin "4") (pinfunction "4_4") (pintype "passive"))
      (node (ref "U$3") (pin "3") (pinfunction "IP-_3") (pintype "bidirectional"))
      (node (ref "U$3") (pin "4") (pinfunction "IP-_4") (pintype "bidirectional"))
    )
    (net (code "69") (name "Net-(K4-Pad5)") (class "Default")
      (node (ref "K4") (pin "5") (pinfunction "5_5") (pintype "passive"))
      (node (ref "U$6") (pin "P$1") (pinfunction "P$1_P$1") (pintype "bidirectional"))
    )
    (net (code "70") (name "Net-(LED1-PadA)") (class "Default")
      (node (ref "LED1") (pin "A") (pinfunction "A_A") (pintype "passive"))
      (node (ref "R53") (pin "2") (pinfunction "2_2") (pintype "passive"))
    )
    (net (code "71") (name "Net-(LED2-PadA)") (class "Default")
      (node (ref "LED2") (pin "A") (pinfunction "A_A") (pintype "passive"))
      (node (ref "R57") (pin "2") (pinfunction "2_2") (pintype "passive"))
    )
    (net (code "72") (name "Net-(LED3-PadA)") (class "Default")
      (node (ref "LED3") (pin "A") (pinfunction "A_A") (pintype "passive"))
      (node (ref "R63") (pin "2") (pinfunction "2_2") (pintype "passive"))
    )
    (net (code "73") (name "Net-(LED4-PadA)") (class "Default")
      (node (ref "LED4") (pin "A") (pinfunction "A_A") (pintype "passive"))
      (node (ref "R66") (pin "2") (pinfunction "2_2") (pintype "passive"))
    )
    (net (code "74") (name "Net-(LED5-PadA)") (class "Default")
      (node (ref "LED5") (pin "A") (pinfunction "A_A") (pintype "passive"))
      (node (ref "R67") (pin "2") (pinfunction "2_2") (pintype "passive"))
    )
    (net (code "75") (name "Net-(Q1-D)") (class "Default")
      (node (ref "D5") (pin "A") (pinfunction "A_A") (pintype "passive"))
      (node (ref "K5") (pin "12") (pinfunction "12_12") (pintype "passive"))
      (node (ref "LED4") (pin "C") (pinfunction "C_C") (pintype "passive"))
      (node (ref "Q1") (pin "3") (pinfunction "D_3") (pintype "bidirectional"))
    )
    (net (code "76") (name "Net-(Q2-D)") (class "Default")
      (node (ref "D4") (pin "A") (pinfunction "A_A") (pintype "passive"))
      (node (ref "K4") (pin "12") (pinfunction "12_12") (pintype "passive"))
      (node (ref "LED5") (pin "C") (pinfunction "C_C") (pintype "passive"))
      (node (ref "Q2") (pin "3") (pinfunction "D_3") (pintype "bidirectional"))
    )
    (net (code "77") (name "Net-(Q3-D)") (class "Default")
      (node (ref "D1") (pin "A") (pinfunction "A_A") (pintype "passive"))
      (node (ref "K3") (pin "12") (pinfunction "12_12") (pintype "passive"))
      (node (ref "LED3") (pin "C") (pinfunction "C_C") (pintype "passive"))
      (node (ref "Q3") (pin "3") (pinfunction "D_3") (pintype "bidirectional"))
    )
    (net (code "78") (name "Net-(Q4-D)") (class "Default")
      (node (ref "D2") (pin "A") (pinfunction "A_A") (pintype "passive"))
      (node (ref "K2") (pin "12") (pinfunction "12_12") (pintype "passive"))
      (node (ref "LED2") (pin "C") (pinfunction "C_C") (pintype "passive"))
      (node (ref "Q4") (pin "3") (pinfunction "D_3") (pintype "bidirectional"))
    )
    (net (code "79") (name "Net-(Q5-D)") (class "Default")
      (node (ref "D3") (pin "A") (pinfunction "A_A") (pintype "passive"))
      (node (ref "K1") (pin "12") (pinfunction "12_12") (pintype "passive"))
      (node (ref "LED1") (pin "C") (pinfunction "C_C") (pintype "passive"))
      (node (ref "Q5") (pin "3") (pinfunction "D_3") (pintype "bidirectional"))
    )
    (net (code "80") (name "Net-(Q7-D)") (class "Default")
      (node (ref "Q7") (pin "3") (pinfunction "D_3") (pintype "bidirectional"))
      (node (ref "R48") (pin "1") (pinfunction "1_1") (pintype "passive"))
    )
    (net (code "81") (name "Net-(Q8-D)") (class "Default")
      (node (ref "Q8") (pin "3") (pinfunction "D_3") (pintype "bidirectional"))
      (node (ref "R52") (pin "1") (pinfunction "1_1") (pintype "passive"))
    )
    (net (code "82") (name "Net-(R1-Pad1)") (class "Default")
      (node (ref "R1") (pin "1") (pinfunction "1_1") (pintype "passive"))
      (node (ref "R48") (pin "2") (pinfunction "2_2") (pintype "passive"))
    )
    (net (code "83") (name "Net-(R21-Pad1)") (class "Default")
      (node (ref "R21") (pin "1") (pinfunction "1_1") (pintype "passive"))
      (node (ref "R26") (pin "2") (pinfunction "2_2") (pintype "passive"))
    )
    (net (code "84") (name "Net-(R23-Pad1)") (class "Default")
      (node (ref "R23") (pin "1") (pinfunction "1_1") (pintype "passive"))
      (node (ref "R27") (pin "2") (pinfunction "2_2") (pintype "passive"))
    )
    (net (code "85") (name "Net-(R25-Pad1)") (class "Default")
      (node (ref "R25") (pin "1") (pinfunction "1_1") (pintype "passive"))
      (node (ref "R28") (pin "2") (pinfunction "2_2") (pintype "passive"))
    )
    (net (code "86") (name "Net-(R26-Pad1)") (class "Default")
      (node (ref "R26") (pin "1") (pinfunction "1_1") (pintype "passive"))
      (node (ref "R29") (pin "2") (pinfunction "2_2") (pintype "passive"))
    )
    (net (code "87") (name "Net-(R27-Pad1)") (class "Default")
      (node (ref "R27") (pin "1") (pinfunction "1_1") (pintype "passive"))
      (node (ref "R30") (pin "2") (pinfunction "2_2") (pintype "passive"))
    )
    (net (code "88") (name "Net-(R28-Pad1)") (class "Default")
      (node (ref "R28") (pin "1") (pinfunction "1_1") (pintype "passive"))
      (node (ref "R31") (pin "2") (pinfunction "2_2") (pintype "passive"))
    )
    (net (code "89") (name "Net-(R49-Pad1)") (class "Default")
      (node (ref "R49") (pin "1") (pinfunction "1_1") (pintype "passive"))
      (node (ref "R52") (pin "2") (pinfunction "2_2") (pintype "passive"))
    )
    (net (code "90") (name "Net-(U$1-FILT)") (class "Default")
      (node (ref "C12") (pin "1") (pinfunction "1_1") (pintype "passive"))
      (node (ref "U$1") (pin "6") (pinfunction "FILT_6") (pintype "bidirectional"))
    )
    (net (code "91") (name "Net-(U$1-VOUT)") (class "Default")
      (node (ref "R50") (pin "1") (pinfunction "1_1") (pintype "passive"))
      (node (ref "U$1") (pin "7") (pinfunction "VOUT_7") (pintype "bidirectional"))
    )
    (net (code "92") (name "Net-(U$3-FILT)") (class "Default")
      (node (ref "C1") (pin "1") (pinfunction "1_1") (pintype "passive"))
      (node (ref "U$3") (pin "6") (pinfunction "FILT_6") (pintype "bidirectional"))
    )
    (net (code "93") (name "Net-(U$3-VOUT)") (class "Default")
      (node (ref "R3") (pin "1") (pinfunction "1_1") (pintype "passive"))
      (node (ref "U$3") (pin "7") (pinfunction "VOUT_7") (pintype "bidirectional"))
    )
    (net (code "94") (name "Net-(U4-PB3)") (class "Default")
      (node (ref "R36") (pin "1") (pinfunction "1_1") (pintype "passive"))
      (node (ref "U4") (pin "39") (pinfunction "PB3_39") (pintype "bidirectional"))
    )
    (net (code "95") (name "Net-(U4-PB4)") (class "Default")
      (node (ref "R37") (pin "1") (pinfunction "1_1") (pintype "passive"))
      (node (ref "U4") (pin "40") (pinfunction "PB4_40") (pintype "bidirectional"))
    )
    (net (code "96") (name "Net-(U4-PB5)") (class "Default")
      (node (ref "R38") (pin "1") (pinfunction "1_1") (pintype "passive"))
      (node (ref "U4") (pin "41") (pinfunction "PB5_41") (pintype "bidirectional"))
    )
    (net (code "97") (name "Net-(U4-PB6)") (class "Default")
      (node (ref "R39") (pin "1") (pinfunction "1_1") (pintype "passive"))
      (node (ref "U4") (pin "42") (pinfunction "PB6_42") (pintype "bidirectional"))
    )
    (net (code "98") (name "Net-(U4-PD0-OSC_IN)") (class "Default")
      (node (ref "C2") (pin "1") (pinfunction "1_1") (pintype "passive"))
      (node (ref "U4") (pin "5") (pinfunction "PD0-OSC_IN_5") (pintype "bidirectional"))
      (node (ref "Y1") (pin "3") (pinfunction "2_3") (pintype "passive"))
    )
    (net (code "99") (name "Net-(U4-PD1-OSC_OUT)") (class "Default")
      (node (ref "C6") (pin "1") (pinfunction "1_1") (pintype "passive"))
      (node (ref "U4") (pin "6") (pinfunction "PD1-OSC_OUT_6") (pintype "bidirectional"))
      (node (ref "Y1") (pin "1") (pinfunction "1_1") (pintype "passive"))
    )
    (net (code "100") (name "Net-(U4-VDDA)") (class "Default")
      (node (ref "C14") (pin "1") (pinfunction "1_1") (pintype "passive"))
      (node (ref "R56") (pin "2") (pinfunction "2_2") (pintype "passive"))
      (node (ref "U4") (pin "9") (pinfunction "VDDA_9") (pintype "power_in"))
    )
    (net (code "101") (name "PILOT1_SENSE") (class "Default")
      (node (ref "IC1") (pin "22") (pinfunction "PA6_22") (pintype "bidirectional"))
      (node (ref "R40") (pin "1") (pinfunction "1_1") (pintype "passive"))
      (node (ref "R41") (pin "2") (pinfunction "2_2") (pintype "passive"))
      (node (ref "R45") (pin "2") (pinfunction "2_2") (pintype "passive"))
    )
    (net (code "102") (name "PILOT_OUT") (class "Default")
      (node (ref "D7") (pin "A") (pinfunction "A_A") (pintype "passive"))
      (node (ref "J7") (pin "10") (pinfunction "10_10") (pintype "passive"))
      (node (ref "R42") (pin "2") (pinfunction "2_2") (pintype "passive"))
    )
    (net (code "103") (name "PILOT_OUT1") (class "Default")
      (node (ref "D6") (pin "A") (pinfunction "A_A") (pintype "passive"))
      (node (ref "J7") (pin "8") (pinfunction "8_8") (pintype "passive"))
      (node (ref "R40") (pin "2") (pinfunction "2_2") (pintype "passive"))
    )
    (net (code "104") (name "PILOT_SENSE") (class "Default")
      (node (ref "IC1") (pin "21") (pinfunction "PA5_21") (pintype "bidirectional"))
      (node (ref "R42") (pin "1") (pinfunction "1_1") (pintype "passive"))
      (node (ref "R43") (pin "2") (pinfunction "2_2") (pintype "passive"))
      (node (ref "R44") (pin "2") (pinfunction "2_2") (pintype "passive"))
    )
    (net (code "105") (name "RCD") (class "Default")
      (node (ref "J4") (pin "39") (pinfunction "39_39") (pintype "passive"))
      (node (ref "J7") (pin "6") (pinfunction "6_6") (pintype "passive"))
      (node (ref "Q6") (pin "3") (pinfunction "D_3") (pintype "bidirectional"))
    )
    (net (code "106") (name "RCD_CTRL") (class "Default")
      (node (ref "IC1") (pin "23") (pinfunction "PA7_23") (pintype "bidirectional"))
      (node (ref "Q6") (pin "1") (pinfunction "G_1") (pintype "bidirectional"))
      (node (ref "R72") (pin "1") (pinfunction "1_1") (pintype "passive"))
    )
    (net (code "107") (name "RCD_TEST") (class "Default")
      (node (ref "J4") (pin "37") (pinfunction "37_37") (pintype "passive"))
      (node (ref "R47") (pin "2") (pinfunction "2_2") (pintype "passive"))
    )
    (net (code "108") (name "RCD_TEST_SENSE") (class "Default")
      (node (ref "IC1") (pin "59") (pinfunction "PB7_59") (pintype "bidirectional"))
      (node (ref "R46") (pin "2") (pinfunction "2_2") (pintype "passive"))
      (node (ref "R47") (pin "1") (pinfunction "1_1") (pintype "passive"))
    )
    (net (code "109") (name "RSA") (class "Default")
      (node (ref "J7") (pin "12") (pinfunction "12_12") (pintype "passive"))
      (node (ref "R69") (pin "1") (pinfunction "1_1") (pintype "passive"))
      (node (ref "U5") (pin "6") (pinfunction "A_6") (pintype "passive"))
    )
    (net (code "110") (name "RSB") (class "Default")
      (node (ref "J7") (pin "14") (pinfunction "14_14") (pintype "passive"))
      (node (ref "R69") (pin "2") (pinfunction "2_2") (pintype "passive"))
      (node (ref "U5") (pin "7") (pinfunction "B_7") (pintype "passive"))
    )
    (net (code "111") (name "SCL") (class "Default")
      (node (ref "IC1") (pin "29") (pinfunction "PB10_29") (pintype "bidirectional"))
      (node (ref "IC2") (pin "6") (pinfunction "SCL_6") (pintype "input"))
      (node (ref "J7") (pin "15") (pinfunction "15_15") (pintype "passive"))
      (node (ref "R61") (pin "1") (pinfunction "1_1") (pintype "passive"))
    )
    (net (code "112") (name "SCLK_HV") (class "Default")
      (node (ref "J8") (pin "14") (pinfunction "14_14") (pintype "passive"))
      (node (ref "R38") (pin "2") (pinfunction "2_2") (pintype "passive"))
    )
    (net (code "113") (name "SCLK_LV") (class "Default")
      (node (ref "J4") (pin "2") (pinfunction "2_2") (pintype "passive"))
      (node (ref "R32") (pin "2") (pinfunction "2_2") (pintype "passive"))
    )
    (net (code "114") (name "SDA") (class "Default")
      (node (ref "IC1") (pin "30") (pinfunction "PB11_30") (pintype "bidirectional"))
      (node (ref "IC2") (pin "5") (pinfunction "SDA_5") (pintype "bidirectional"))
      (node (ref "J7") (pin "13") (pinfunction "13_13") (pintype "passive"))
      (node (ref "R62") (pin "1") (pinfunction "1_1") (pintype "passive"))
    )
    (net (code "115") (name "SPI2_MISO") (class "Default")
      (node (ref "IC1") (pin "35") (pinfunction "PB14_35") (pintype "bidirectional"))
      (node (ref "J7") (pin "5") (pinfunction "5_5") (pintype "passive"))
    )
    (net (code "116") (name "SPI2_MOSI") (class "Default")
      (node (ref "IC1") (pin "36") (pinfunction "PB15_36") (pintype "bidirectional"))
      (node (ref "J7") (pin "7") (pinfunction "7_7") (pintype "passive"))
    )
    (net (code "117") (name "SPI2_SCLK") (class "Default")
      (node (ref "IC1") (pin "34") (pinfunction "PB13_34") (pintype "bidirectional"))
      (node (ref "J7") (pin "9") (pinfunction "9_9") (pintype "passive"))
    )
    (net (code "118") (name "STM_BOOT0") (class "Default")
      (node (ref "J1") (pin "4") (pinfunction "4_4") (pintype "passive"))
      (node (ref "J4") (pin "23") (pinfunction "23_23") (pintype "passive"))
      (node (ref "J4") (pin "5") (pinfunction "5_5") (pintype "passive"))
    )
    (net (code "119") (name "STM_HV_BOOT0") (class "Default")
      (node (ref "R19") (pin "2") (pinfunction "2_2") (pintype "passive"))
      (node (ref "U$5") (pin "13") (pinfunction "B2_13") (pintype "output"))
      (node (ref "U4") (pin "44") (pinfunction "BOOT0_44") (pintype "bidirectional"))
    )
    (net (code "120") (name "STM_HV_BOOT0_ISO") (class "Default")
      (node (ref "J3") (pin "4") (pinfunction "4_4") (pintype "passive"))
      (node (ref "U$5") (pin "4") (pinfunction "A2_4") (pintype "input"))
    )
    (net (code "121") (name "STM_HV_RST") (class "Default")
      (node (ref "R18") (pin "1") (pinfunction "1_1") (pintype "passive"))
      (node (ref "U$5") (pin "14") (pinfunction "B1_14") (pintype "output"))
      (node (ref "U4") (pin "7") (pinfunction "NRST_7") (pintype "bidirectional"))
    )
    (net (code "122") (name "STM_HV_RST_ISO") (class "Default")
      (node (ref "J11") (pin "3") (pinfunction "3_3") (pintype "passive"))
      (node (ref "J3") (pin "3") (pinfunction "3_3") (pintype "passive"))
      (node (ref "U$5") (pin "3") (pinfunction "A1_3") (pintype "input"))
    )
    (net (code "123") (name "STM_HV_RX") (class "Default")
      (node (ref "U$5") (pin "12") (pinfunction "B3_12") (pintype "output"))
      (node (ref "U4") (pin "31") (pinfunction "PA10_31") (pintype "bidirectional"))
    )
    (net (code "124") (name "STM_HV_RX_ISO") (class "Default")
      (node (ref "J3") (pin "2") (pinfunction "2_2") (pintype "passive"))
      (node (ref "U$5") (pin "5") (pinfunction "A3_5") (pintype "input"))
    )
    (net (code "125") (name "STM_HV_SWCLK") (class "Default")
      (node (ref "U$2") (pin "11") (pinfunction "B4_11") (pintype "output"))
      (node (ref "U4") (pin "37") (pinfunction "PA14_37") (pintype "bidirectional"))
    )
    (net (code "126") (name "STM_HV_SWCLK_ISO") (class "Default")
      (node (ref "J11") (pin "2") (pinfunction "2_2") (pintype "passive"))
      (node (ref "U$2") (pin "6") (pinfunction "A4_6") (pintype "input"))
    )
    (net (code "127") (name "STM_HV_SWDIO") (class "Default")
      (node (ref "U$2") (pin "12") (pinfunction "B3_12") (pintype "output"))
      (node (ref "U4") (pin "34") (pinfunction "PA13_34") (pintype "bidirectional"))
    )
    (net (code "128") (name "STM_HV_SWDIO_ISO") (class "Default")
      (node (ref "J11") (pin "1") (pinfunction "1_1") (pintype "passive"))
      (node (ref "U$2") (pin "5") (pinfunction "A3_5") (pintype "input"))
    )
    (net (code "129") (name "STM_HV_TX") (class "Default")
      (node (ref "U$5") (pin "11") (pinfunction "B4_11") (pintype "output"))
      (node (ref "U4") (pin "30") (pinfunction "PA9_30") (pintype "bidirectional"))
    )
    (net (code "130") (name "STM_HV_TX_ISO") (class "Default")
      (node (ref "J3") (pin "1") (pinfunction "1_1") (pintype "passive"))
      (node (ref "U$5") (pin "6") (pinfunction "A4_6") (pintype "input"))
    )
    (net (code "131") (name "STM_LV_BOOT0") (class "Default")
      (node (ref "IC1") (pin "60") (pinfunction "BOOT0_60") (pintype "input"))
      (node (ref "J2") (pin "4") (pinfunction "4_4") (pintype "passive"))
      (node (ref "R60") (pin "2") (pinfunction "2_2") (pintype "passive"))
    )
    (net (code "132") (name "STM_LV_RST") (class "Default")
      (node (ref "IC1") (pin "7") (pinfunction "NRST_7") (pintype "bidirectional"))
      (node (ref "J2") (pin "3") (pinfunction "3_3") (pintype "passive"))
      (node (ref "J9") (pin "3") (pinfunction "3_3") (pintype "passive"))
      (node (ref "R59") (pin "1") (pinfunction "1_1") (pintype "passive"))
    )
    (net (code "133") (name "STM_LV_RX") (class "Default")
      (node (ref "IC1") (pin "43") (pinfunction "PA10_43") (pintype "bidirectional"))
      (node (ref "J2") (pin "2") (pinfunction "2_2") (pintype "passive"))
    )
    (net (code "134") (name "STM_LV_SWCLK") (class "Default")
      (node (ref "IC1") (pin "49") (pinfunction "PA14_49") (pintype "bidirectional"))
      (node (ref "J9") (pin "2") (pinfunction "2_2") (pintype "passive"))
    )
    (net (code "135") (name "STM_LV_SWDIO") (class "Default")
      (node (ref "IC1") (pin "46") (pinfunction "PA13_46") (pintype "bidirectional"))
      (node (ref "J9") (pin "1") (pinfunction "1_1") (pintype "passive"))
    )
    (net (code "136") (name "STM_LV_TX") (class "Default")
      (node (ref "IC1") (pin "42") (pinfunction "PA9_42") (pintype "bidirectional"))
      (node (ref "J2") (pin "1") (pinfunction "1_1") (pintype "passive"))
    )
    (net (code "137") (name "STM_RST") (class "Default")
      (node (ref "J1") (pin "3") (pinfunction "3_3") (pintype "passive"))
      (node (ref "J10") (pin "3") (pinfunction "3_3") (pintype "passive"))
      (node (ref "J4") (pin "9") (pinfunction "9_9") (pintype "passive"))
    )
    (net (code "138") (name "STM_RX") (class "Default")
      (node (ref "J1") (pin "2") (pinfunction "2_2") (pintype "passive"))
      (node (ref "J4") (pin "36") (pinfunction "36_36") (pintype "passive"))
    )
    (net (code "139") (name "STM_SWCLK") (class "Default")
      (node (ref "J10") (pin "2") (pinfunction "2_2") (pintype "passive"))
      (node (ref "J4") (pin "1") (pinfunction "1_1") (pintype "passive"))
    )
    (net (code "140") (name "STM_SWDIO") (class "Default")
      (node (ref "J10") (pin "1") (pinfunction "1_1") (pintype "passive"))
      (node (ref "J4") (pin "40") (pinfunction "40_40") (pintype "passive"))
    )
    (net (code "141") (name "STM_TX") (class "Default")
      (node (ref "J1") (pin "1") (pinfunction "1_1") (pintype "passive"))
      (node (ref "J4") (pin "38") (pinfunction "38_38") (pintype "passive"))
    )
    (net (code "142") (name "TA_CURR_RELAY") (class "Default")
      (node (ref "Q2") (pin "1") (pinfunction "G_1") (pintype "bidirectional"))
      (node (ref "R68") (pin "2") (pinfunction "2_2") (pintype "passive"))
      (node (ref "U4") (pin "45") (pinfunction "PB8_45") (pintype "bidirectional"))
    )
    (net (code "143") (name "VCC") (class "Default")
      (node (ref "C18") (pin "2") (pinfunction "2_2") (pintype "passive"))
      (node (ref "C21") (pin "+") (pinfunction "+_+") (pintype "passive"))
      (node (ref "C29") (pin "1") (pinfunction "1_1") (pintype "passive"))
      (node (ref "C3") (pin "1") (pinfunction "1_1") (pintype "passive"))
      (node (ref "C38") (pin "1") (pinfunction "1_1") (pintype "passive"))
      (node (ref "C39") (pin "1") (pinfunction "1_1") (pintype "passive"))
      (node (ref "C4") (pin "1") (pinfunction "1_1") (pintype "passive"))
      (node (ref "C42") (pin "+") (pinfunction "+_+") (pintype "passive"))
      (node (ref "C43") (pin "+") (pinfunction "+_+") (pintype "passive"))
      (node (ref "C5") (pin "+") (pinfunction "+_+") (pintype "passive"))
      (node (ref "D2") (pin "C") (pinfunction "C_C") (pintype "passive"))
      (node (ref "D3") (pin "C") (pinfunction "C_C") (pintype "passive"))
      (node (ref "DC2") (pin "2") (pinfunction "+VIN_2") (pintype "passive"))
      (node (ref "K1") (pin "1") (pinfunction "1_1") (pintype "passive"))
      (node (ref "K2") (pin "1") (pinfunction "1_1") (pintype "passive"))
      (node (ref "R53") (pin "1") (pinfunction "1_1") (pintype "passive"))
      (node (ref "R57") (pin "1") (pinfunction "1_1") (pintype "passive"))
      (node (ref "R73") (pin "2") (pinfunction "2_2") (pintype "passive"))
      (node (ref "U$3") (pin "1") (pinfunction "IP+_1") (pintype "bidirectional"))
      (node (ref "U$3") (pin "2") (pinfunction "IP+_2") (pintype "bidirectional"))
      (node (ref "U$3") (pin "8") (pinfunction "VCC_8") (pintype "bidirectional"))
      (node (ref "U$4") (pin "V+") (pinfunction "V+_V+") (pintype "output"))
      (node (ref "U3") (pin "1") (pinfunction "IN_1") (pintype "input"))
      (node (ref "U3") (pin "3") (pinfunction "EN_3") (pintype "input"))
    )
    (net (code "144") (name "VCC_OUT") (class "Default")
      (node (ref "FUSE") (pin "1") (pinfunction "1_1") (pintype "passive"))
      (node (ref "J4") (pin "13") (pinfunction "13_13") (pintype "passive"))
      (node (ref "J4") (pin "27") (pinfunction "27_27") (pintype "passive"))
      (node (ref "J4") (pin "29") (pinfunction "29_29") (pintype "passive"))
      (node (ref "J4") (pin "31") (pinfunction "31_31") (pintype "passive"))
      (node (ref "J4") (pin "7") (pinfunction "7_7") (pintype "passive"))
      (node (ref "J4") (pin "8") (pinfunction "8_8") (pintype "passive"))
      (node (ref "R11") (pin "2") (pinfunction "2_2") (pintype "passive"))
      (node (ref "R5") (pin "1") (pinfunction "1_1") (pintype "passive"))
    )
    (net (code "145") (name "VDD") (class "Default")
      (node (ref "C10") (pin "1") (pinfunction "1_1") (pintype "passive"))
      (node (ref "C22") (pin "+") (pinfunction "+_+") (pintype "passive"))
      (node (ref "C7") (pin "1") (pinfunction "1_1") (pintype "passive"))
      (node (ref "C8") (pin "1") (pinfunction "1_1") (pintype "passive"))
      (node (ref "C9") (pin "1") (pinfunction "1_1") (pintype "passive"))
      (node (ref "R18") (pin "2") (pinfunction "2_2") (pintype "passive"))
      (node (ref "R56") (pin "1") (pinfunction "1_1") (pintype "passive"))
      (node (ref "U$2") (pin "10") (pinfunction "EN2_10") (pintype "input"))
      (node (ref "U$2") (pin "16") (pinfunction "VDD2_16") (pintype "power_in"))
      (node (ref "U$5") (pin "10") (pinfunction "EN2_10") (pintype "input"))
      (node (ref "U$5") (pin "16") (pinfunction "VDD2_16") (pintype "power_in"))
      (node (ref "U1") (pin "5") (pinfunction "OUT_5") (pintype "passive"))
      (node (ref "U4") (pin "1") (pinfunction "VBAT_1") (pintype "input"))
      (node (ref "U4") (pin "24") (pinfunction "VDD_1_24") (pintype "bidirectional"))
      (node (ref "U4") (pin "36") (pinfunction "VDD_2_36") (pintype "power_in"))
      (node (ref "U4") (pin "48") (pinfunction "VDD_3_48") (pintype "power_in"))
    )
    (net (code "146") (name "VDD_TEST") (class "Default")
      (node (ref "J8") (pin "9") (pinfunction "9_9") (pintype "passive"))
      (node (ref "R17") (pin "2") (pinfunction "2_2") (pintype "passive"))
    )
    (net (code "147") (name "_AUX2") (class "Default")
      (node (ref "IC1") (pin "44") (pinfunction "PA11_44") (pintype "bidirectional"))
      (node (ref "J7") (pin "4") (pinfunction "4_4") (pintype "passive"))
    )
    (net (code "148") (name "_AUX3") (class "Default")
      (node (ref "IC1") (pin "45") (pinfunction "PA12_45") (pintype "bidirectional"))
      (node (ref "J7") (pin "2") (pinfunction "2_2") (pintype "passive"))
    )
    (net (code "149") (name "unconnected-(IC1A-PA3-Pad17)") (class "Default")
      (node (ref "IC1") (pin "17") (pinfunction "PA3_17") (pintype "bidirectional"))
    )
    (net (code "150") (name "unconnected-(IC1A-PA4-Pad20)") (class "Default")
      (node (ref "IC1") (pin "20") (pinfunction "PA4_20") (pintype "bidirectional"))
    )
    (net (code "151") (name "unconnected-(IC1A-PC0-Pad8)") (class "Default")
      (node (ref "IC1") (pin "8") (pinfunction "PC0_8") (pintype "bidirectional"))
    )
    (net (code "152") (name "unconnected-(IC1A-PC1-Pad9)") (class "Default")
      (node (ref "IC1") (pin "9") (pinfunction "PC1_9") (pintype "bidirectional"))
    )
    (net (code "153") (name "unconnected-(IC1A-PC2-Pad10)") (class "Default")
      (node (ref "IC1") (pin "10") (pinfunction "PC2_10") (pintype "bidirectional"))
    )
    (net (code "154") (name "unconnected-(IC1A-PC3-Pad11)") (class "Default")
      (node (ref "IC1") (pin "11") (pinfunction "PC3_11") (pintype "bidirectional"))
    )
    (net (code "155") (name "unconnected-(IC1A-PC4-Pad24)") (class "Default")
      (node (ref "IC1") (pin "24") (pinfunction "PC4_24") (pintype "bidirectional"))
    )
    (net (code "156") (name "unconnected-(IC1A-PC5-Pad25)") (class "Default")
      (node (ref "IC1") (pin "25") (pinfunction "PC5_25") (pintype "bidirectional"))
    )
    (net (code "157") (name "unconnected-(IC1A-PC10-Pad51)") (class "Default")
      (node (ref "IC1") (pin "51") (pinfunction "PC10_51") (pintype "bidirectional"))
    )
    (net (code "158") (name "unconnected-(IC1A-PC11-Pad52)") (class "Default")
      (node (ref "IC1") (pin "52") (pinfunction "PC11_52") (pintype "bidirectional"))
    )
    (net (code "159") (name "unconnected-(IC1A-PC12-Pad53)") (class "Default")
      (node (ref "IC1") (pin "53") (pinfunction "PC12_53") (pintype "bidirectional"))
    )
    (net (code "160") (name "unconnected-(IC1A-PC13-Pad2)") (class "Default")
      (node (ref "IC1") (pin "2") (pinfunction "PC13_2") (pintype "bidirectional"))
    )
    (net (code "161") (name "unconnected-(IC1A-PD2-Pad54)") (class "Default")
      (node (ref "IC1") (pin "54") (pinfunction "PD2_54") (pintype "bidirectional"))
    )
    (net (code "162") (name "unconnected-(J4-Pad10)") (class "Default")
      (node (ref "J4") (pin "10") (pinfunction "10_10") (pintype "passive"))
    )
    (net (code "163") (name "unconnected-(J4-Pad12)") (class "Default")
      (node (ref "J4") (pin "12") (pinfunction "12_12") (pintype "passive"))
    )
    (net (code "164") (name "unconnected-(J4-Pad14)") (class "Default")
      (node (ref "J4") (pin "14") (pinfunction "14_14") (pintype "passive"))
    )
    (net (code "165") (name "unconnected-(J4-Pad16)") (class "Default")
      (node (ref "J4") (pin "16") (pinfunction "16_16") (pintype "passive"))
    )
    (net (code "166") (name "unconnected-(J4-Pad18)") (class "Default")
      (node (ref "J4") (pin "18") (pinfunction "18_18") (pintype "passive"))
    )
    (net (code "167") (name "unconnected-(J4-Pad20)") (class "Default")
      (node (ref "J4") (pin "20") (pinfunction "20_20") (pintype "passive"))
    )
    (net (code "168") (name "unconnected-(J4-Pad22)") (class "Default")
      (node (ref "J4") (pin "22") (pinfunction "22_22") (pintype "passive"))
    )
    (net (code "169") (name "unconnected-(J4-Pad24)") (class "Default")
      (node (ref "J4") (pin "24") (pinfunction "24_24") (pintype "passive"))
    )
    (net (code "170") (name "unconnected-(J4-Pad25)") (class "Default")
      (node (ref "J4") (pin "25") (pinfunction "25_25") (pintype "passive"))
    )
    (net (code "171") (name "unconnected-(J4-Pad26)") (class "Default")
      (node (ref "J4") (pin "26") (pinfunction "26_26") (pintype "passive"))
    )
    (net (code "172") (name "unconnected-(J4-Pad28)") (class "Default")
      (node (ref "J4") (pin "28") (pinfunction "28_28") (pintype "passive"))
    )
    (net (code "173") (name "unconnected-(J4-Pad30)") (class "Default")
      (node (ref "J4") (pin "30") (pinfunction "30_30") (pintype "passive"))
    )
    (net (code "174") (name "unconnected-(J4-Pad32)") (class "Default")
      (node (ref "J4") (pin "32") (pinfunction "32_32") (pintype "passive"))
    )
    (net (code "175") (name "unconnected-(J4-Pad34)") (class "Default")
      (node (ref "J4") (pin "34") (pinfunction "34_34") (pintype "passive"))
    )
    (net (code "176") (name "unconnected-(J7-Pad16)") (class "Default")
      (node (ref "J7") (pin "16") (pinfunction "16_16") (pintype "passive"))
    )
    (net (code "177") (name "unconnected-(J8-Pad7)") (class "Default")
      (node (ref "J8") (pin "7") (pinfunction "7_7") (pintype "passive"))
    )
    (net (code "178") (name "unconnected-(J8-Pad8)") (class "Default")
      (node (ref "J8") (pin "8") (pinfunction "8_8") (pintype "passive"))
    )
    (net (code "179") (name "unconnected-(J8-Pad10)") (class "Default")
      (node (ref "J8") (pin "10") (pinfunction "10_10") (pintype "passive"))
    )
    (net (code "180") (name "unconnected-(J8-Pad12)") (class "Default")
      (node (ref "J8") (pin "12") (pinfunction "12_12") (pintype "passive"))
    )
    (net (code "181") (name "unconnected-(K1-Pad3)") (class "Default")
      (node (ref "K1") (pin "3") (pinfunction "3_3") (pintype "passive"))
    )
    (net (code "182") (name "unconnected-(K1-Pad4)") (class "Default")
      (node (ref "K1") (pin "4") (pinfunction "4_4") (pintype "passive"))
    )
    (net (code "183") (name "unconnected-(K1-Pad5)") (class "Default")
      (node (ref "K1") (pin "5") (pinfunction "5_5") (pintype "passive"))
    )
    (net (code "184") (name "unconnected-(K1-Pad10)") (class "Default")
      (node (ref "K1") (pin "10") (pinfunction "10_10") (pintype "passive"))
    )
    (net (code "185") (name "unconnected-(K2-Pad3)") (class "Default")
      (node (ref "K2") (pin "3") (pinfunction "3_3") (pintype "passive"))
    )
    (net (code "186") (name "unconnected-(K2-Pad8)") (class "Default")
      (node (ref "K2") (pin "8") (pinfunction "8_8") (pintype "passive"))
    )
    (net (code "187") (name "unconnected-(K2-Pad9)") (class "Default")
      (node (ref "K2") (pin "9") (pinfunction "9_9") (pintype "passive"))
    )
    (net (code "188") (name "unconnected-(K2-Pad10)") (class "Default")
      (node (ref "K2") (pin "10") (pinfunction "10_10") (pintype "passive"))
    )
    (net (code "189") (name "unconnected-(K3-Pad3)") (class "Default")
      (node (ref "K3") (pin "3") (pinfunction "3_3") (pintype "passive"))
    )
    (net (code "190") (name "unconnected-(K3-Pad10)") (class "Default")
      (node (ref "K3") (pin "10") (pinfunction "10_10") (pintype "passive"))
    )
    (net (code "191") (name "unconnected-(K4-Pad3)") (class "Default")
      (node (ref "K4") (pin "3") (pinfunction "3_3") (pintype "passive"))
    )
    (net (code "192") (name "unconnected-(K4-Pad10)") (class "Default")
      (node (ref "K4") (pin "10") (pinfunction "10_10") (pintype "passive"))
    )
    (net (code "193") (name "unconnected-(K5-Pad3)") (class "Default")
      (node (ref "K5") (pin "3") (pinfunction "3_3") (pintype "passive"))
    )
    (net (code "194") (name "unconnected-(K5-Pad10)") (class "Default")
      (node (ref "K5") (pin "10") (pinfunction "10_10") (pintype "passive"))
    )
    (net (code "195") (name "unconnected-(U$2-A1-Pad3)") (class "Default")
      (node (ref "U$2") (pin "3") (pinfunction "A1_3") (pintype "input"))
    )
    (net (code "196") (name "unconnected-(U$2-A2-Pad4)") (class "Default")
      (node (ref "U$2") (pin "4") (pinfunction "A2_4") (pintype "input"))
    )
    (net (code "197") (name "unconnected-(U$2-B1-Pad14)") (class "Default")
      (node (ref "U$2") (pin "14") (pinfunction "B1_14") (pintype "output"))
    )
    (net (code "198") (name "unconnected-(U$2-B2-Pad13)") (class "Default")
      (node (ref "U$2") (pin "13") (pinfunction "B2_13") (pintype "output"))
    )
    (net (code "199") (name "unconnected-(U1-NC-Pad4)") (class "Default")
      (node (ref "U1") (pin "4") (pinfunction "NC_4") (pintype "no_connect"))
    )
    (net (code "200") (name "unconnected-(U3-NC-Pad4)") (class "Default")
      (node (ref "U3") (pin "4") (pinfunction "NC_4") (pintype "no_connect"))
    )
    (net (code "201") (name "unconnected-(U4-PA6-Pad16)") (class "Default")
      (node (ref "U4") (pin "16") (pinfunction "PA6_16") (pintype "bidirectional"))
    )
    (net (code "202") (name "unconnected-(U4-PA7-Pad17)") (class "Default")
      (node (ref "U4") (pin "17") (pinfunction "PA7_17") (pintype "bidirectional"))
    )
    (net (code "203") (name "unconnected-(U4-PA8-Pad29)") (class "Default")
      (node (ref "U4") (pin "29") (pinfunction "PA8_29") (pintype "bidirectional"))
    )
    (net (code "204") (name "unconnected-(U4-PA12-Pad33)") (class "Default")
      (node (ref "U4") (pin "33") (pinfunction "PA12_33") (pintype "bidirectional"))
    )
    (net (code "205") (name "unconnected-(U4-PB0-Pad18)") (class "Default")
      (node (ref "U4") (pin "18") (pinfunction "PB0_18") (pintype "bidirectional"))
    )
    (net (code "206") (name "unconnected-(U4-PB1-Pad19)") (class "Default")
      (node (ref "U4") (pin "19") (pinfunction "PB1_19") (pintype "bidirectional"))
    )
    (net (code "207") (name "unconnected-(U4-PB7-Pad43)") (class "Default")
      (node (ref "U4") (pin "43") (pinfunction "PB7_43") (pintype "bidirectional"))
    )
    (net (code "208") (name "unconnected-(U4-PB10-Pad21)") (class "Default")
      (node (ref "U4") (pin "21") (pinfunction "PB10_21") (pintype "bidirectional"))
    )
    (net (code "209") (name "unconnected-(U4-PB11-Pad22)") (class "Default")
      (node (ref "U4") (pin "22") (pinfunction "PB11_22") (pintype "bidirectional"))
    )
    (net (code "210") (name "unconnected-(U4-PB12-Pad25)") (class "Default")
      (node (ref "U4") (pin "25") (pinfunction "PB12_25") (pintype "bidirectional"))
    )
    (net (code "211") (name "unconnected-(U4-PB13-Pad26)") (class "Default")
      (node (ref "U4") (pin "26") (pinfunction "PB13_26") (pintype "bidirectional"))
    )
    (net (code "212") (name "unconnected-(U4-PB14-Pad27)") (class "Default")
      (node (ref "U4") (pin "27") (pinfunction "PB14_27") (pintype "bidirectional"))
    )
    (net (code "213") (name "unconnected-(U4-PB15-Pad28)") (class "Default")
      (node (ref "U4") (pin "28") (pinfunction "PB15_28") (pintype "bidirectional"))
    )
    (net (code "214") (name "unconnected-(U4-PC13-TAMPER-RTC-Pad2)") (class "Default")
      (node (ref "U4") (pin "2") (pinfunction "PC13-TAMPER-RTC_2") (pintype "bidirectional"))
    )
    (net (code "215") (name "unconnected-(U4-PC14-OSC32_IN-Pad3)") (class "Default")
      (node (ref "U4") (pin "3") (pinfunction "PC14-OSC32_IN_3") (pintype "bidirectional"))
    )
    (net (code "216") (name "unconnected-(U4-PC15-OSC32_OUT-Pad4)") (class "Default")
      (node (ref "U4") (pin "4") (pinfunction "PC15-OSC32_OUT_4") (pintype "bidirectional"))
    )
  )
)
